# OSSIComms.net
KiCad netlist of a schematic drawn in EAGLE
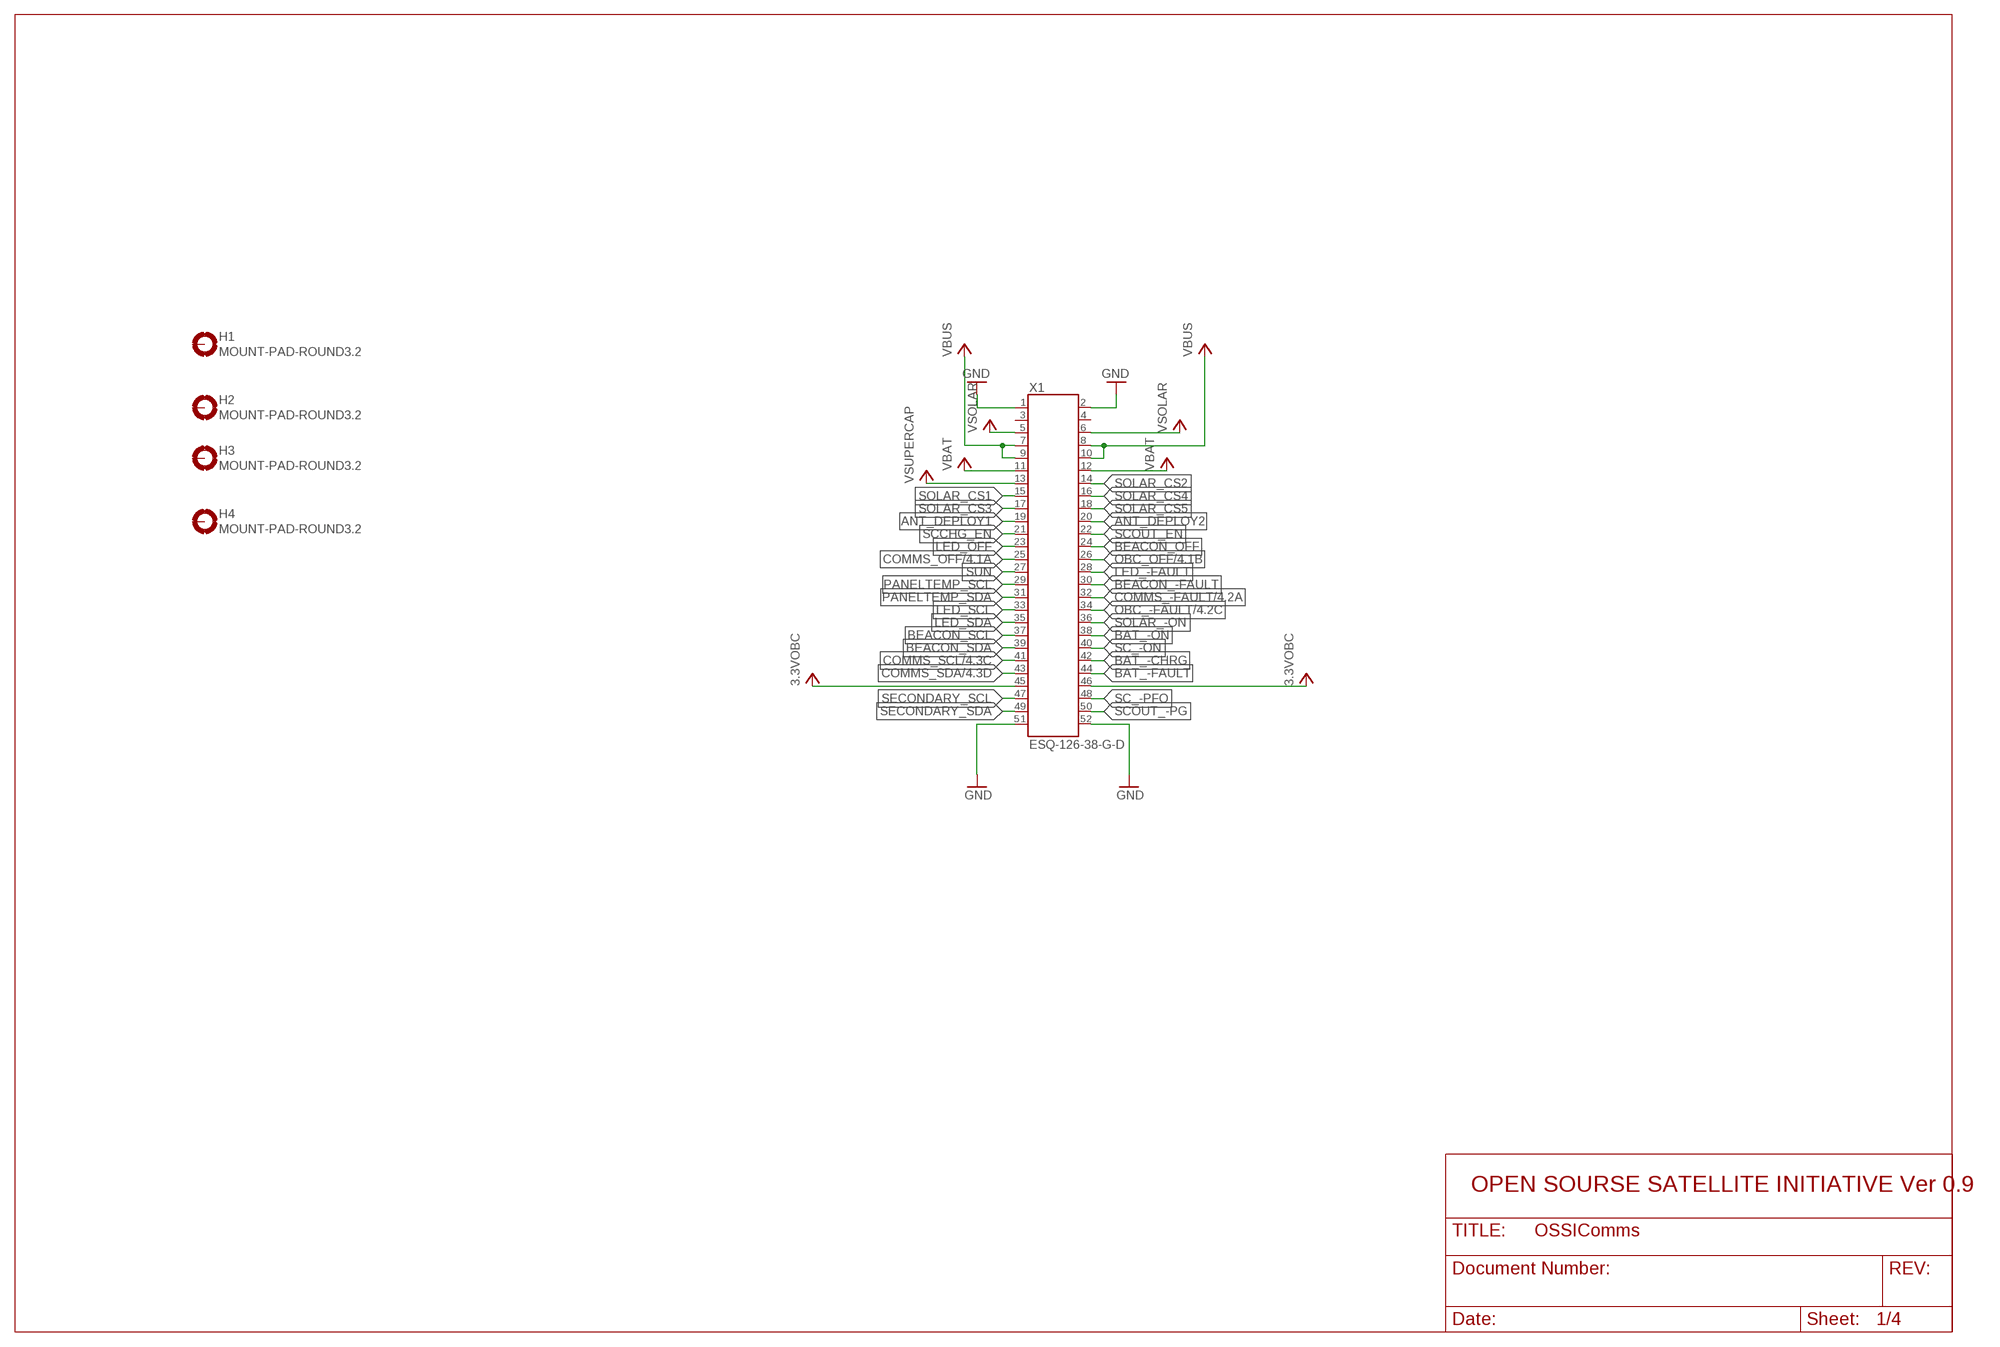
[diagram p0: schematic, sheet 1]
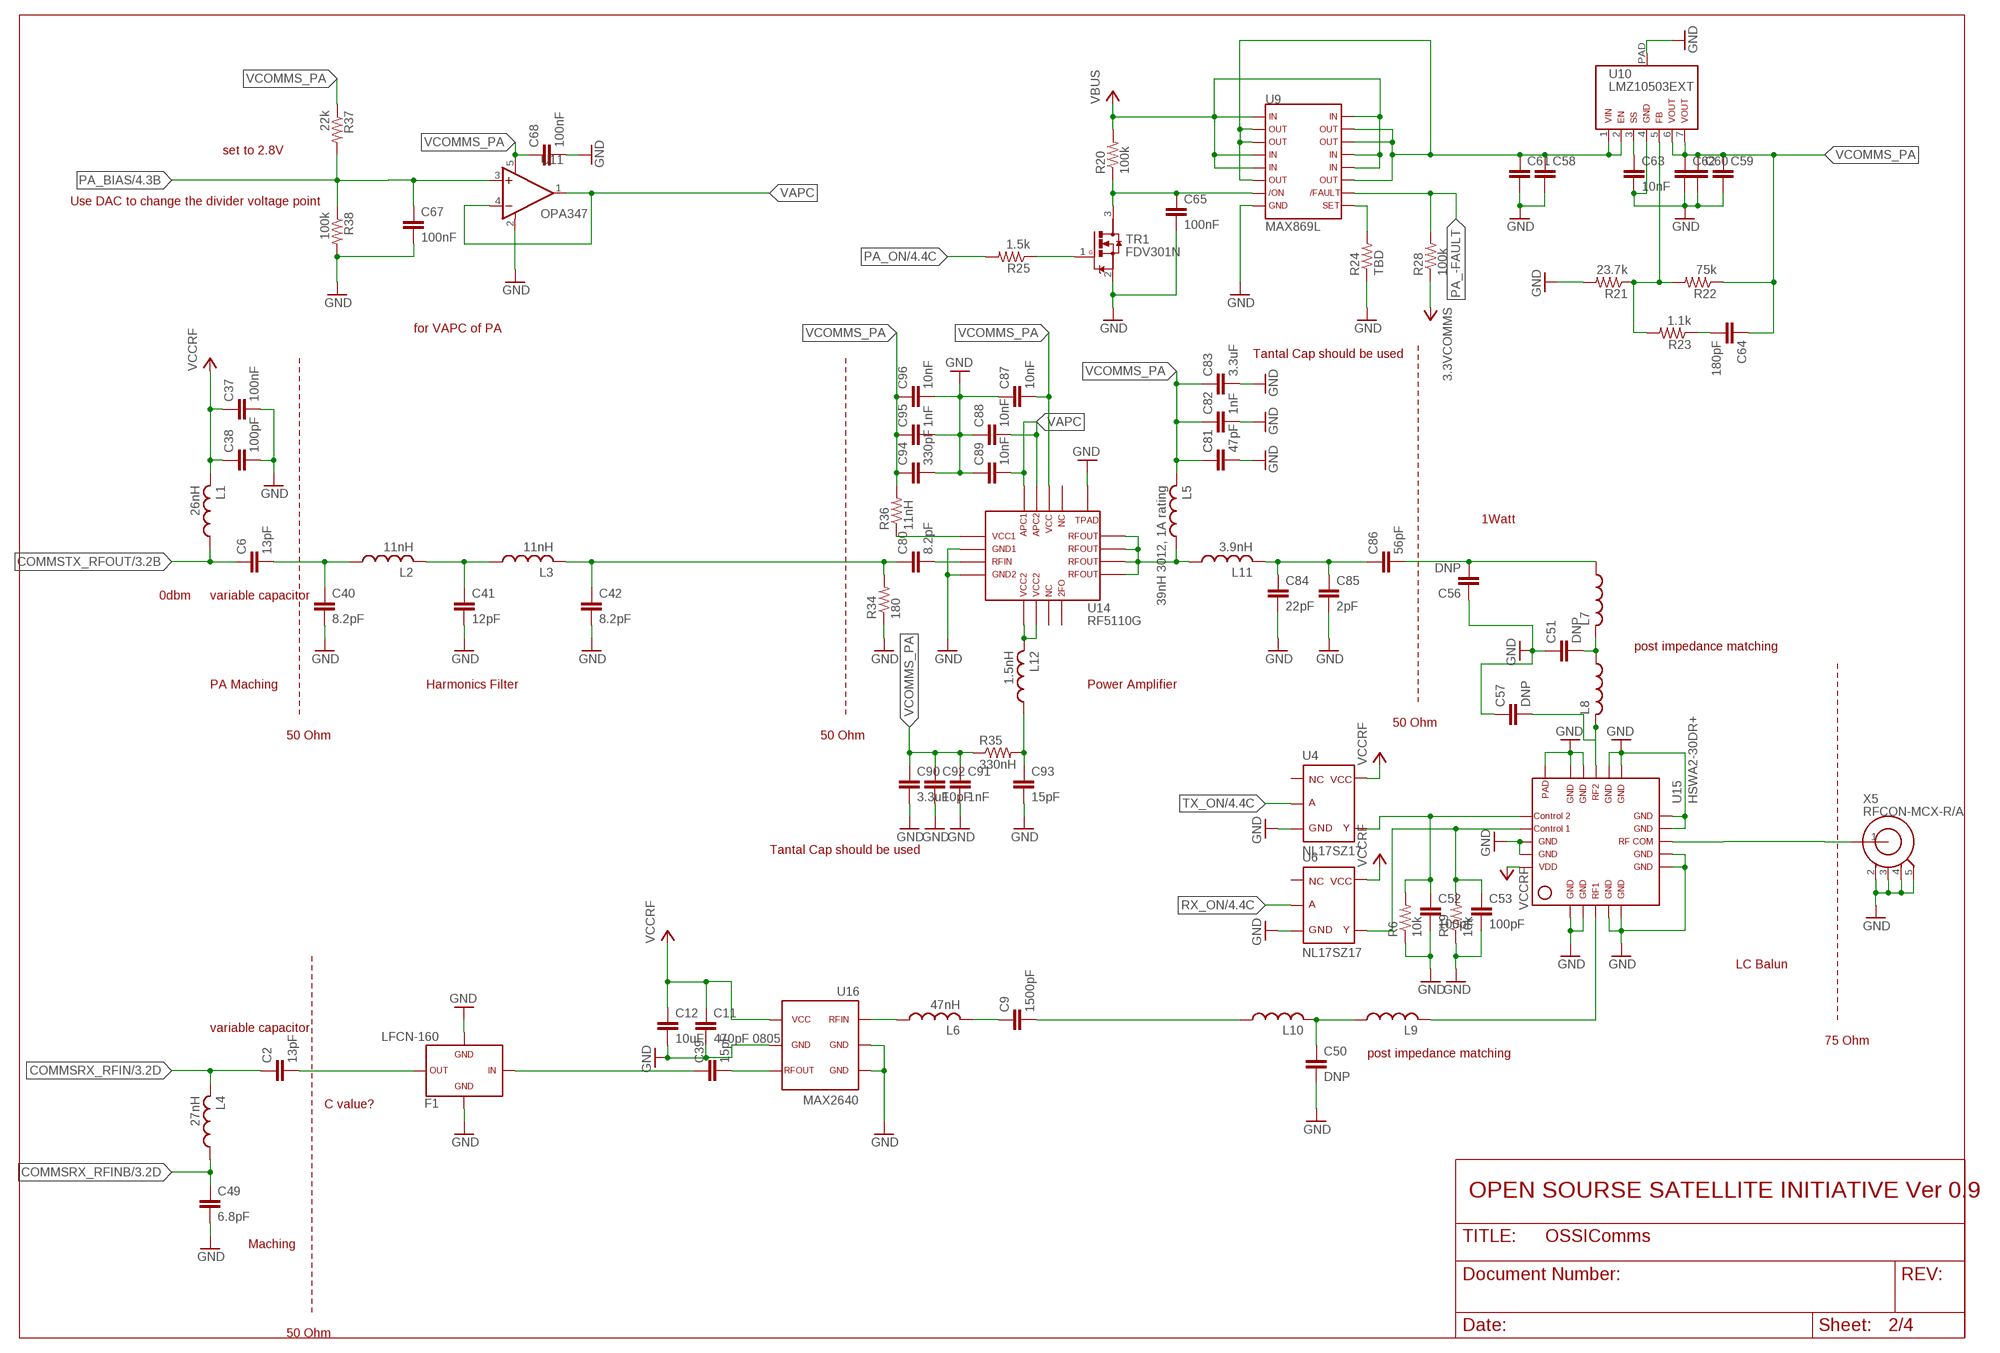
[diagram p1: schematic, sheet 2]
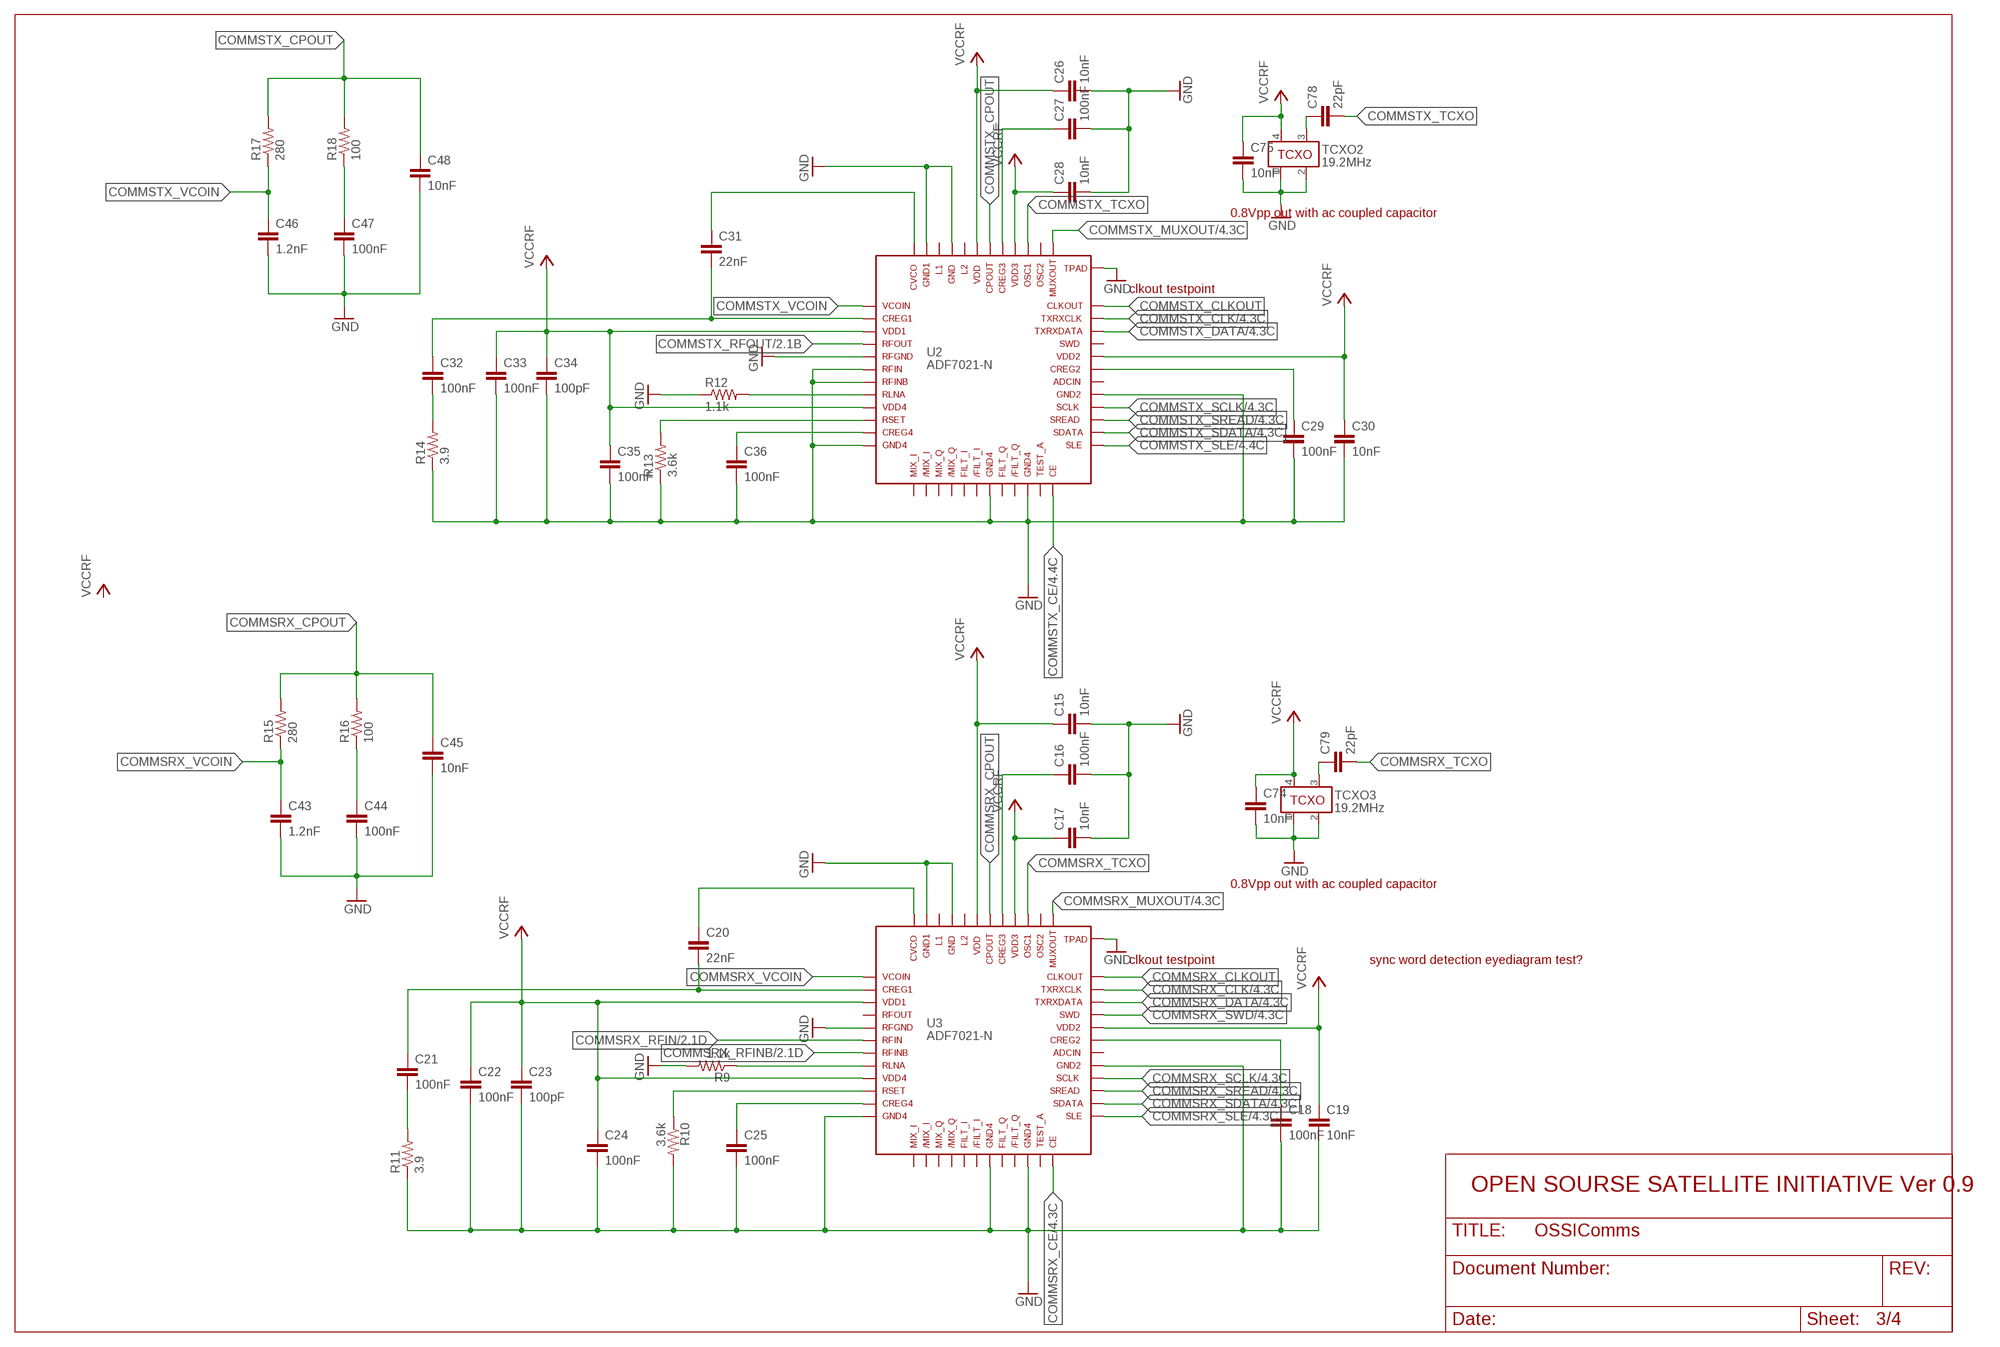
[diagram p2: schematic, sheet 3]
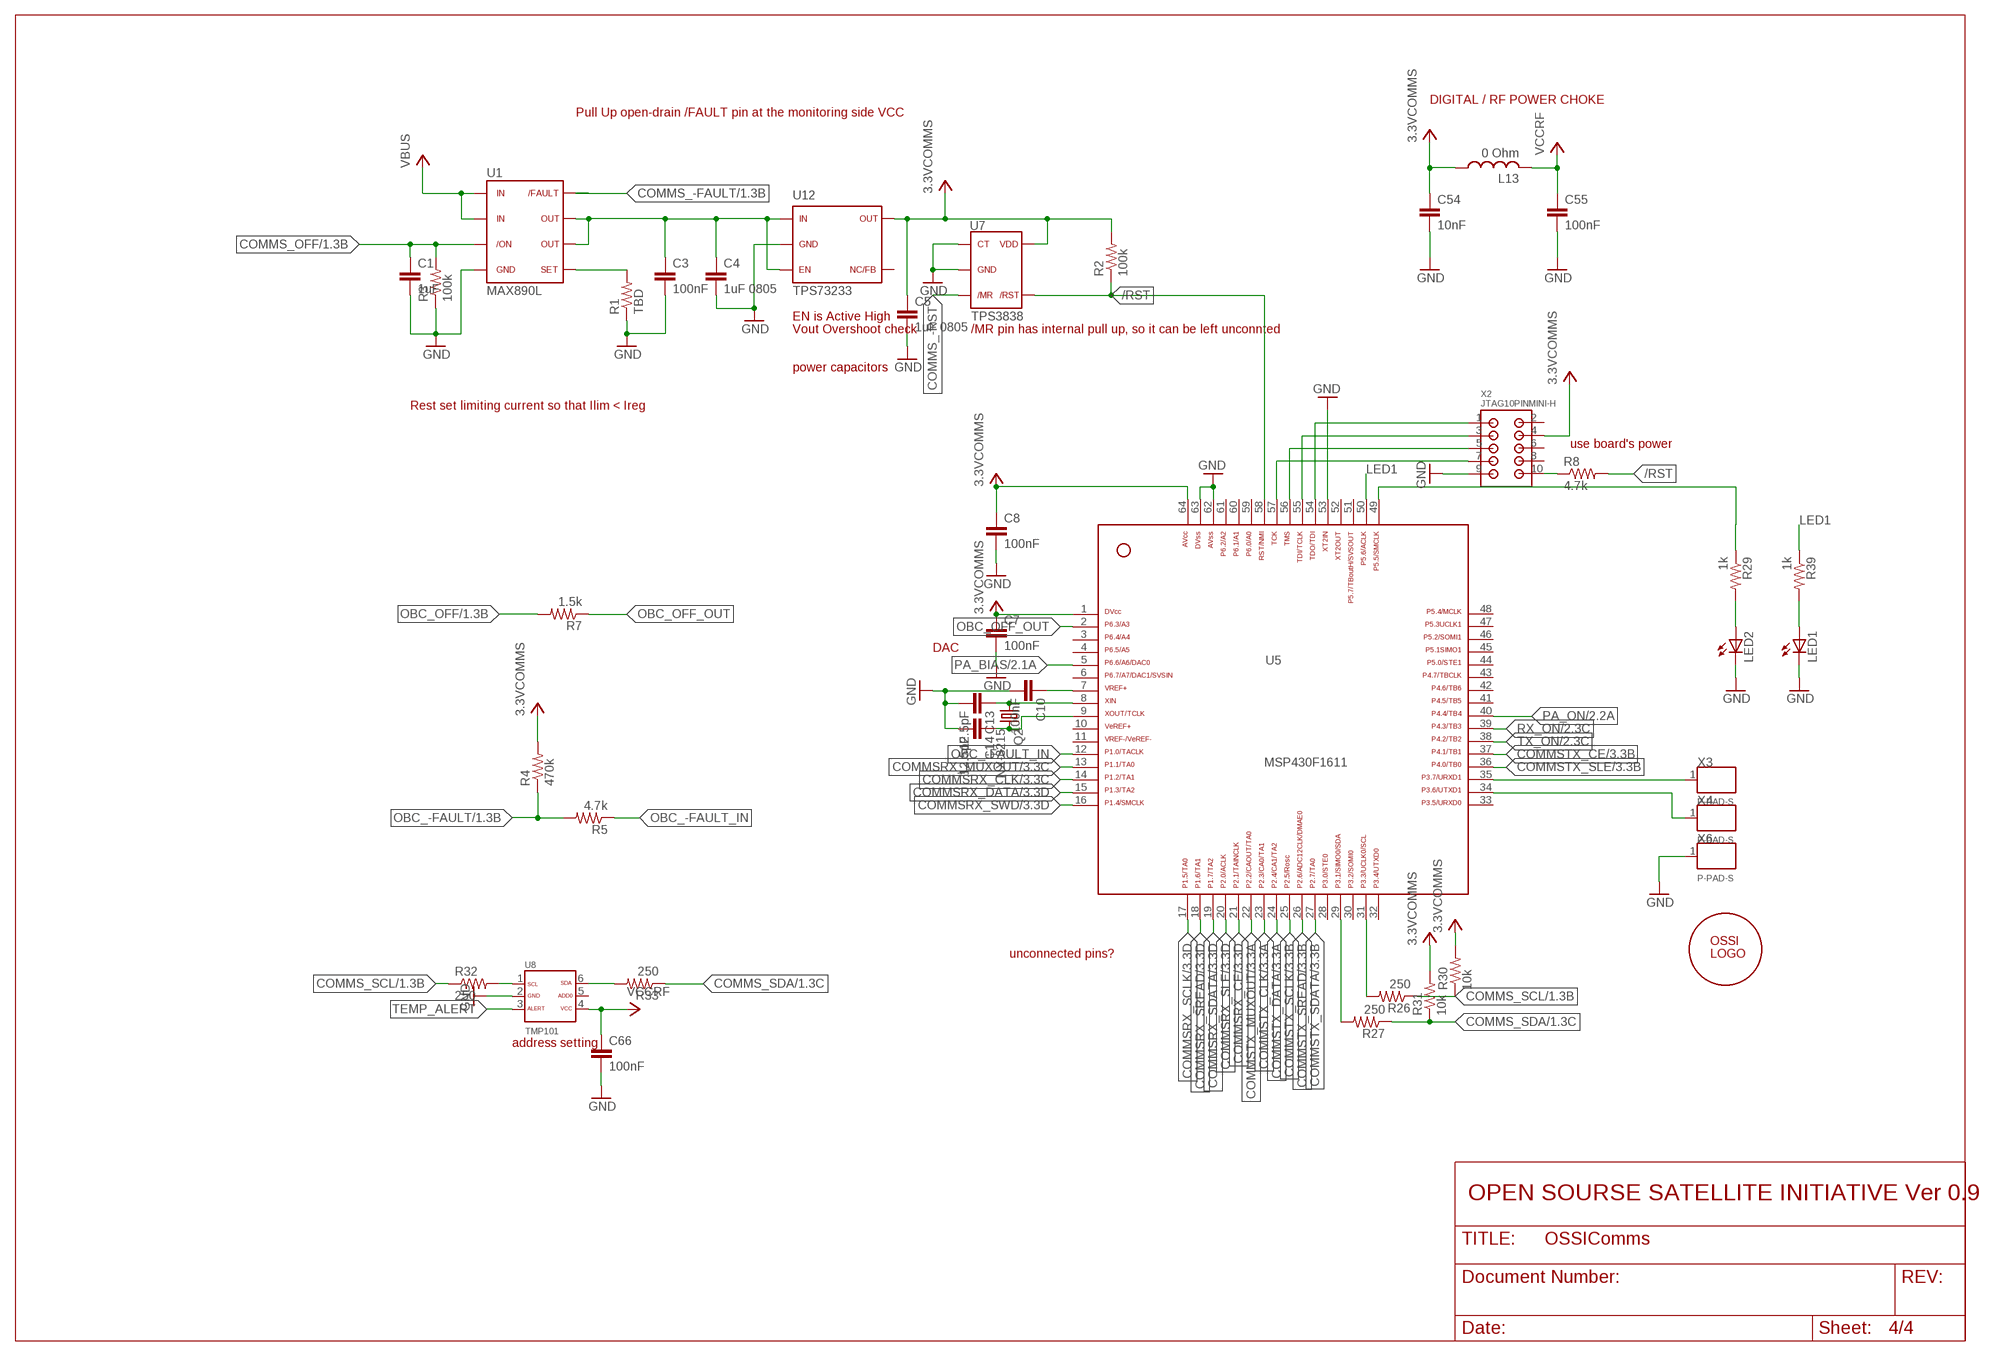
[diagram p3: schematic, sheet 4]

(export (version "E")
  (design (tool "Eeschema 10.0.6"))
  (components
    (comp (ref "C1")
      (value "1uF")
      (footprint "eagle-import:C0603(1608)")
      (libsource (lib "eagle-import") (part "C0603(1608)"))
    )
    (comp (ref "C3")
      (value "100nF")
      (footprint "eagle-import:C0603(1608)")
      (libsource (lib "eagle-import") (part "C0603(1608)"))
    )
    (comp (ref "C4")
      (value "1uF 0805")
      (footprint "eagle-import:C0805(2012)")
      (libsource (lib "eagle-import") (part "C0805(2012)"))
    )
    (comp (ref "C5")
      (value "1uF 0805")
      (footprint "eagle-import:C0805(2012)")
      (libsource (lib "eagle-import") (part "C0805(2012)"))
    )
    (comp (ref "C7")
      (value "100nF")
      (footprint "eagle-import:C0603(1608)")
      (libsource (lib "eagle-import") (part "C0603(1608)"))
    )
    (comp (ref "C8")
      (value "100nF")
      (footprint "eagle-import:C0603(1608)")
      (libsource (lib "eagle-import") (part "C0603(1608)"))
    )
    (comp (ref "C10")
      (value "100nF")
      (footprint "eagle-import:C0603(1608)")
      (libsource (lib "eagle-import") (part "C0603(1608)"))
    )
    (comp (ref "C13")
      (value "12.5pF")
      (footprint "eagle-import:C0603(1608)")
      (libsource (lib "eagle-import") (part "C0603(1608)"))
    )
    (comp (ref "C14")
      (value "12.5pF")
      (footprint "eagle-import:C0603(1608)")
      (libsource (lib "eagle-import") (part "C0603(1608)"))
    )
    (comp (ref "C54")
      (value "10nF")
      (footprint "eagle-import:C0603(1608)")
      (libsource (lib "eagle-import") (part "C0603(1608)"))
    )
    (comp (ref "C55")
      (value "100nF")
      (footprint "eagle-import:C0603(1608)")
      (libsource (lib "eagle-import") (part "C0603(1608)"))
    )
    (comp (ref "C66")
      (value "100nF")
      (footprint "eagle-import:C0603(1608)")
      (libsource (lib "eagle-import") (part "C0603(1608)"))
    )
    (comp (ref "L13")
      (value "0 Ohm")
      (footprint "eagle-import:L0805(2012)")
      (libsource (lib "eagle-import") (part "L0805(2012)"))
    )
    (comp (ref "LED1")
      (value "LEDCHIPLED_0603")
      (footprint "eagle-import:CHIPLED_0603")
      (libsource (lib "eagle-import") (part "LEDCHIPLED_0603"))
    )
    (comp (ref "LED2")
      (value "LEDCHIPLED_0603")
      (footprint "eagle-import:CHIPLED_0603")
      (libsource (lib "eagle-import") (part "LEDCHIPLED_0603"))
    )
    (comp (ref "Q2")
      (value "NX-3215")
      (footprint "eagle-import:NX-3215")
      (libsource (lib "eagle-import") (part "NX-3215"))
    )
    (comp (ref "R1")
      (value "TBD")
      (footprint "eagle-import:R0603(1608)")
      (libsource (lib "eagle-import") (part "R0603(1608)"))
    )
    (comp (ref "R2")
      (value "100k")
      (footprint "eagle-import:R0603(1608)")
      (libsource (lib "eagle-import") (part "R0603(1608)"))
    )
    (comp (ref "R3")
      (value "100k")
      (footprint "eagle-import:R0603(1608)")
      (libsource (lib "eagle-import") (part "R0603(1608)"))
    )
    (comp (ref "R4")
      (value "470k")
      (footprint "eagle-import:R0603(1608)")
      (libsource (lib "eagle-import") (part "R0603(1608)"))
    )
    (comp (ref "R5")
      (value "4.7k")
      (footprint "eagle-import:R0603(1608)")
      (libsource (lib "eagle-import") (part "R0603(1608)"))
    )
    (comp (ref "R7")
      (value "1.5k")
      (footprint "eagle-import:R0603(1608)")
      (libsource (lib "eagle-import") (part "R0603(1608)"))
    )
    (comp (ref "R8")
      (value "4.7k")
      (footprint "eagle-import:R0603(1608)")
      (libsource (lib "eagle-import") (part "R0603(1608)"))
    )
    (comp (ref "R26")
      (value "250")
      (footprint "eagle-import:R0603(1608)")
      (libsource (lib "eagle-import") (part "R0603(1608)"))
    )
    (comp (ref "R27")
      (value "250")
      (footprint "eagle-import:R0603(1608)")
      (libsource (lib "eagle-import") (part "R0603(1608)"))
    )
    (comp (ref "R29")
      (value "1k")
      (footprint "eagle-import:R0603(1608)")
      (libsource (lib "eagle-import") (part "R0603(1608)"))
    )
    (comp (ref "R30")
      (value "10k")
      (footprint "eagle-import:R0603(1608)")
      (libsource (lib "eagle-import") (part "R0603(1608)"))
    )
    (comp (ref "R31")
      (value "10k")
      (footprint "eagle-import:R0603(1608)")
      (libsource (lib "eagle-import") (part "R0603(1608)"))
    )
    (comp (ref "R32")
      (value "250")
      (footprint "eagle-import:R0603(1608)")
      (libsource (lib "eagle-import") (part "R0603(1608)"))
    )
    (comp (ref "R33")
      (value "250")
      (footprint "eagle-import:R0603(1608)")
      (libsource (lib "eagle-import") (part "R0603(1608)"))
    )
    (comp (ref "R39")
      (value "1k")
      (footprint "eagle-import:R0603(1608)")
      (libsource (lib "eagle-import") (part "R0603(1608)"))
    )
    (comp (ref "U$1")
      (value "OSSILOGORECT")
      (footprint "eagle-import:OSSILOGORECT1005")
      (libsource (lib "eagle-import") (part "OSSILOGORECT"))
    )
    (comp (ref "U1")
      (value "MAX890L")
      (footprint "eagle-import:SO8")
      (libsource (lib "eagle-import") (part "MAX890L"))
    )
    (comp (ref "U5")
      (value "MSP430F1611")
      (footprint "eagle-import:PM_PAG64")
      (libsource (lib "eagle-import") (part "MSP430F1611"))
    )
    (comp (ref "U7")
      (value "TPS3838")
      (footprint "eagle-import:SOT23-5DBV")
      (libsource (lib "eagle-import") (part "TPS3838"))
    )
    (comp (ref "U8")
      (value "TMP101")
      (footprint "eagle-import:SOT23-6DBV")
      (libsource (lib "eagle-import") (part "TMP101"))
    )
    (comp (ref "U12")
      (value "TPS73233")
      (footprint "eagle-import:SOT23-5DBV")
      (libsource (lib "eagle-import") (part "TPS73233"))
    )
    (comp (ref "X2")
      (value "JTAG10PINMINI-H")
      (footprint "eagle-import:M50-3200545")
      (libsource (lib "eagle-import") (part "JTAG10PINMINI-H"))
    )
    (comp (ref "X3")
      (value "P-PAD-S")
      (footprint "eagle-import:P-PAD-S")
      (libsource (lib "eagle-import") (part "P-PAD-S"))
    )
    (comp (ref "X4")
      (value "P-PAD-S")
      (footprint "eagle-import:P-PAD-S")
      (libsource (lib "eagle-import") (part "P-PAD-S"))
    )
    (comp (ref "X6")
      (value "P-PAD-S")
      (footprint "eagle-import:P-PAD-S")
      (libsource (lib "eagle-import") (part "P-PAD-S"))
    )
    (comp (ref "C2")
      (value "13pF")
      (footprint "eagle-import:C0603(1608)")
      (libsource (lib "eagle-import") (part "C0603(1608)"))
    )
    (comp (ref "C6")
      (value "13pF")
      (footprint "eagle-import:C0603(1608)")
      (libsource (lib "eagle-import") (part "C0603(1608)"))
    )
    (comp (ref "C9")
      (value "1500pF")
      (footprint "eagle-import:C0603(1608)")
      (libsource (lib "eagle-import") (part "C0603(1608)"))
    )
    (comp (ref "C11")
      (value "470pF 0805")
      (footprint "eagle-import:C0805(2012)")
      (libsource (lib "eagle-import") (part "C0805(2012)"))
    )
    (comp (ref "C12")
      (value "10uF")
      (footprint "eagle-import:C1206-GCM31")
      (libsource (lib "eagle-import") (part "C1206(3216)-GCM31"))
    )
    (comp (ref "C37")
      (value "100nF")
      (footprint "eagle-import:C0603(1608)")
      (libsource (lib "eagle-import") (part "C0603(1608)"))
    )
    (comp (ref "C38")
      (value "100pF")
      (footprint "eagle-import:C0603(1608)")
      (libsource (lib "eagle-import") (part "C0603(1608)"))
    )
    (comp (ref "C39")
      (value "15pF")
      (footprint "eagle-import:C0603(1608)")
      (libsource (lib "eagle-import") (part "C0603(1608)"))
    )
    (comp (ref "C40")
      (value "8.2pF")
      (footprint "eagle-import:C0603(1608)")
      (libsource (lib "eagle-import") (part "C0603(1608)"))
    )
    (comp (ref "C41")
      (value "12pF")
      (footprint "eagle-import:C0603(1608)")
      (libsource (lib "eagle-import") (part "C0603(1608)"))
    )
    (comp (ref "C42")
      (value "8.2pF")
      (footprint "eagle-import:C0603(1608)")
      (libsource (lib "eagle-import") (part "C0603(1608)"))
    )
    (comp (ref "C49")
      (value "6.8pF")
      (footprint "eagle-import:C0603(1608)")
      (libsource (lib "eagle-import") (part "C0603(1608)"))
    )
    (comp (ref "C50")
      (value "DNP")
      (footprint "eagle-import:C0603(1608)")
      (libsource (lib "eagle-import") (part "C0603(1608)"))
    )
    (comp (ref "C51")
      (value "DNP")
      (footprint "eagle-import:C0603(1608)")
      (libsource (lib "eagle-import") (part "C0603(1608)"))
    )
    (comp (ref "C52")
      (value "100pF")
      (footprint "eagle-import:C0603(1608)")
      (libsource (lib "eagle-import") (part "C0603(1608)"))
    )
    (comp (ref "C53")
      (value "100pF")
      (footprint "eagle-import:C0603(1608)")
      (libsource (lib "eagle-import") (part "C0603(1608)"))
    )
    (comp (ref "C56")
      (value "DNP")
      (footprint "eagle-import:C0603(1608)")
      (libsource (lib "eagle-import") (part "C0603(1608)"))
    )
    (comp (ref "C57")
      (value "DNP")
      (footprint "eagle-import:C0603(1608)")
      (libsource (lib "eagle-import") (part "C0603(1608)"))
    )
    (comp (ref "C58")
      (value "C1210(3225)-GCM32")
      (footprint "eagle-import:C1210-GCM32")
      (libsource (lib "eagle-import") (part "C1210(3225)-GCM32"))
    )
    (comp (ref "C59")
      (value "C1210(3225)-GCM32")
      (footprint "eagle-import:C1210-GCM32")
      (libsource (lib "eagle-import") (part "C1210(3225)-GCM32"))
    )
    (comp (ref "C60")
      (value "C1210(3225)-GCM32")
      (footprint "eagle-import:C1210-GCM32")
      (libsource (lib "eagle-import") (part "C1210(3225)-GCM32"))
    )
    (comp (ref "C61")
      (value "C1210(3225)-GCM32")
      (footprint "eagle-import:C1210-GCM32")
      (libsource (lib "eagle-import") (part "C1210(3225)-GCM32"))
    )
    (comp (ref "C62")
      (value "C0805(2012)")
      (footprint "eagle-import:C0805(2012)")
      (libsource (lib "eagle-import") (part "C0805(2012)"))
    )
    (comp (ref "C63")
      (value "10nF")
      (footprint "eagle-import:C0603(1608)")
      (libsource (lib "eagle-import") (part "C0603(1608)"))
    )
    (comp (ref "C64")
      (value "180pF")
      (footprint "eagle-import:C0603(1608)")
      (libsource (lib "eagle-import") (part "C0603(1608)"))
    )
    (comp (ref "C65")
      (value "100nF")
      (footprint "eagle-import:C0603(1608)")
      (libsource (lib "eagle-import") (part "C0603(1608)"))
    )
    (comp (ref "C67")
      (value "100nF")
      (footprint "eagle-import:C0603(1608)")
      (libsource (lib "eagle-import") (part "C0603(1608)"))
    )
    (comp (ref "C68")
      (value "100nF")
      (footprint "eagle-import:C0603(1608)")
      (libsource (lib "eagle-import") (part "C0603(1608)"))
    )
    (comp (ref "C80")
      (value "8.2pF")
      (footprint "eagle-import:C0603(1608)")
      (libsource (lib "eagle-import") (part "C0603(1608)"))
    )
    (comp (ref "C81")
      (value "47pF")
      (footprint "eagle-import:C0603(1608)")
      (libsource (lib "eagle-import") (part "C0603(1608)"))
    )
    (comp (ref "C82")
      (value "1nF")
      (footprint "eagle-import:C0603(1608)")
      (libsource (lib "eagle-import") (part "C0603(1608)"))
    )
    (comp (ref "C83")
      (value "3.3uF")
      (footprint "eagle-import:C1210-TMK325")
      (libsource (lib "eagle-import") (part "C1210(3225)-TMK325"))
    )
    (comp (ref "C84")
      (value "22pF")
      (footprint "eagle-import:C0603(1608)")
      (libsource (lib "eagle-import") (part "C0603(1608)"))
    )
    (comp (ref "C85")
      (value "2pF")
      (footprint "eagle-import:C0603(1608)")
      (libsource (lib "eagle-import") (part "C0603(1608)"))
    )
    (comp (ref "C86")
      (value "56pF")
      (footprint "eagle-import:C0603(1608)")
      (libsource (lib "eagle-import") (part "C0603(1608)"))
    )
    (comp (ref "C87")
      (value "10nF")
      (footprint "eagle-import:C0603(1608)")
      (libsource (lib "eagle-import") (part "C0603(1608)"))
    )
    (comp (ref "C88")
      (value "10nF")
      (footprint "eagle-import:C0603(1608)")
      (libsource (lib "eagle-import") (part "C0603(1608)"))
    )
    (comp (ref "C89")
      (value "10nF")
      (footprint "eagle-import:C0603(1608)")
      (libsource (lib "eagle-import") (part "C0603(1608)"))
    )
    (comp (ref "C90")
      (value "3.3uF")
      (footprint "eagle-import:C1210-TMK325")
      (libsource (lib "eagle-import") (part "C1210(3225)-TMK325"))
    )
    (comp (ref "C91")
      (value "1nF")
      (footprint "eagle-import:C0603(1608)")
      (libsource (lib "eagle-import") (part "C0603(1608)"))
    )
    (comp (ref "C92")
      (value "10pF")
      (footprint "eagle-import:C0603(1608)")
      (libsource (lib "eagle-import") (part "C0603(1608)"))
    )
    (comp (ref "C93")
      (value "15pF")
      (footprint "eagle-import:C0603(1608)")
      (libsource (lib "eagle-import") (part "C0603(1608)"))
    )
    (comp (ref "C94")
      (value "330pF")
      (footprint "eagle-import:C0603(1608)")
      (libsource (lib "eagle-import") (part "C0603(1608)"))
    )
    (comp (ref "C95")
      (value "1nF")
      (footprint "eagle-import:C0603(1608)")
      (libsource (lib "eagle-import") (part "C0603(1608)"))
    )
    (comp (ref "C96")
      (value "10nF")
      (footprint "eagle-import:C0603(1608)")
      (libsource (lib "eagle-import") (part "C0603(1608)"))
    )
    (comp (ref "F1")
      (value "LFCN-160")
      (footprint "eagle-import:LFCN")
      (libsource (lib "eagle-import") (part "LFCN-160"))
    )
    (comp (ref "L1")
      (value "26nH")
      (footprint "eagle-import:L0603(1608)")
      (libsource (lib "eagle-import") (part "L0603(1608)"))
    )
    (comp (ref "L2")
      (value "11nH")
      (footprint "eagle-import:L0603(1608)")
      (libsource (lib "eagle-import") (part "L0603(1608)"))
    )
    (comp (ref "L3")
      (value "11nH")
      (footprint "eagle-import:L0603(1608)")
      (libsource (lib "eagle-import") (part "L0603(1608)"))
    )
    (comp (ref "L4")
      (value "27nH")
      (footprint "eagle-import:L0603(1608)")
      (libsource (lib "eagle-import") (part "L0603(1608)"))
    )
    (comp (ref "L5")
      (value "39nH 3012, 1A rating")
      (footprint "eagle-import:NR3012")
      (libsource (lib "eagle-import") (part "LNR3012"))
    )
    (comp (ref "L6")
      (value "47nH")
      (footprint "eagle-import:L0603(1608)")
      (libsource (lib "eagle-import") (part "L0603(1608)"))
    )
    (comp (ref "L7")
      (value "L0603(1608)")
      (footprint "eagle-import:L0603(1608)")
      (libsource (lib "eagle-import") (part "L0603(1608)"))
    )
    (comp (ref "L8")
      (value "L0603(1608)")
      (footprint "eagle-import:L0603(1608)")
      (libsource (lib "eagle-import") (part "L0603(1608)"))
    )
    (comp (ref "L9")
      (value "L0603(1608)")
      (footprint "eagle-import:L0603(1608)")
      (libsource (lib "eagle-import") (part "L0603(1608)"))
    )
    (comp (ref "L10")
      (value "L0603(1608)")
      (footprint "eagle-import:L0603(1608)")
      (libsource (lib "eagle-import") (part "L0603(1608)"))
    )
    (comp (ref "L11")
      (value "3.9nH")
      (footprint "eagle-import:L0603(1608)")
      (libsource (lib "eagle-import") (part "L0603(1608)"))
    )
    (comp (ref "L12")
      (value "1.5nH")
      (footprint "eagle-import:L0603(1608)")
      (libsource (lib "eagle-import") (part "L0603(1608)"))
    )
    (comp (ref "R6")
      (value "10k")
      (footprint "eagle-import:R0603(1608)")
      (libsource (lib "eagle-import") (part "R0603(1608)"))
    )
    (comp (ref "R19")
      (value "10k")
      (footprint "eagle-import:R0603(1608)")
      (libsource (lib "eagle-import") (part "R0603(1608)"))
    )
    (comp (ref "R20")
      (value "100k")
      (footprint "eagle-import:R0603(1608)")
      (libsource (lib "eagle-import") (part "R0603(1608)"))
    )
    (comp (ref "R21")
      (value "23.7k")
      (footprint "eagle-import:R0603(1608)")
      (libsource (lib "eagle-import") (part "R0603(1608)"))
    )
    (comp (ref "R22")
      (value "75k")
      (footprint "eagle-import:R0603(1608)")
      (libsource (lib "eagle-import") (part "R0603(1608)"))
    )
    (comp (ref "R23")
      (value "1.1k")
      (footprint "eagle-import:R0603(1608)")
      (libsource (lib "eagle-import") (part "R0603(1608)"))
    )
    (comp (ref "R24")
      (value "TBD")
      (footprint "eagle-import:R0603(1608)")
      (libsource (lib "eagle-import") (part "R0603(1608)"))
    )
    (comp (ref "R25")
      (value "1.5k")
      (footprint "eagle-import:R0603(1608)")
      (libsource (lib "eagle-import") (part "R0603(1608)"))
    )
    (comp (ref "R28")
      (value "100k")
      (footprint "eagle-import:R0603(1608)")
      (libsource (lib "eagle-import") (part "R0603(1608)"))
    )
    (comp (ref "R34")
      (value "180")
      (footprint "eagle-import:R0603(1608)")
      (libsource (lib "eagle-import") (part "R0603(1608)"))
    )
    (comp (ref "R35")
      (value "330nH")
      (footprint "eagle-import:R0603(1608)")
      (libsource (lib "eagle-import") (part "R0603(1608)"))
    )
    (comp (ref "R36")
      (value "11nH")
      (footprint "eagle-import:R0603(1608)")
      (libsource (lib "eagle-import") (part "R0603(1608)"))
    )
    (comp (ref "R37")
      (value "22k")
      (footprint "eagle-import:R0603(1608)")
      (libsource (lib "eagle-import") (part "R0603(1608)"))
    )
    (comp (ref "R38")
      (value "100k")
      (footprint "eagle-import:R0603(1608)")
      (libsource (lib "eagle-import") (part "R0603(1608)"))
    )
    (comp (ref "TR1")
      (value "FDV301N")
      (footprint "eagle-import:SOT23")
      (libsource (lib "eagle-import") (part "FDV301N"))
    )
    (comp (ref "U4")
      (value "NL17SZ17")
      (footprint "eagle-import:SOT-553")
      (libsource (lib "eagle-import") (part "NL17SZ17"))
    )
    (comp (ref "U6")
      (value "NL17SZ17")
      (footprint "eagle-import:SOT-553")
      (libsource (lib "eagle-import") (part "NL17SZ17"))
    )
    (comp (ref "U9")
      (value "MAX869L")
      (footprint "eagle-import:16QSOP")
      (libsource (lib "eagle-import") (part "MAX869L"))
    )
    (comp (ref "U10")
      (value "LMZ10503EXT")
      (footprint "eagle-import:TO-PMOD-7")
      (libsource (lib "eagle-import") (part "LMZ10503EXT"))
    )
    (comp (ref "U11")
      (value "OPA347")
      (footprint "eagle-import:SOT23-5DBV")
      (libsource (lib "eagle-import") (part "OPA347"))
    )
    (comp (ref "U14")
      (value "RF5110G")
      (footprint "eagle-import:RF5110G")
      (libsource (lib "eagle-import") (part "RF5110G"))
    )
    (comp (ref "U15")
      (value "HSWA2-30DR+")
      (footprint "eagle-import:DG983-1")
      (libsource (lib "eagle-import") (part "HSWA2-30DR+"))
    )
    (comp (ref "U16")
      (value "MAX2640")
      (footprint "eagle-import:SOT23-6")
      (libsource (lib "eagle-import") (part "MAX2640"))
    )
    (comp (ref "X5")
      (value "RFCON-MCX-R/A")
      (footprint "eagle-import:MCX-R_A")
      (libsource (lib "eagle-import") (part "RFCON-MCX-R/A"))
    )
    (comp (ref "H1")
      (value "MOUNT-PAD-ROUND3.2")
      (footprint "eagle-import:3.2-PAD-ROUND")
      (libsource (lib "eagle-import") (part "MOUNT-PAD-ROUND3.2"))
    )
    (comp (ref "H2")
      (value "MOUNT-PAD-ROUND3.2")
      (footprint "eagle-import:3.2-PAD-ROUND")
      (libsource (lib "eagle-import") (part "MOUNT-PAD-ROUND3.2"))
    )
    (comp (ref "H3")
      (value "MOUNT-PAD-ROUND3.2")
      (footprint "eagle-import:3.2-PAD-ROUND")
      (libsource (lib "eagle-import") (part "MOUNT-PAD-ROUND3.2"))
    )
    (comp (ref "H4")
      (value "MOUNT-PAD-ROUND3.2")
      (footprint "eagle-import:3.2-PAD-ROUND")
      (libsource (lib "eagle-import") (part "MOUNT-PAD-ROUND3.2"))
    )
    (comp (ref "X1")
      (value "ESQ-126-38-G-D")
      (footprint "eagle-import:ESQ-126-XX-X-D")
      (libsource (lib "eagle-import") (part "ESQ-126-38-G-D"))
    )
    (comp (ref "C15")
      (value "10nF")
      (footprint "eagle-import:C0603(1608)")
      (libsource (lib "eagle-import") (part "C0603(1608)"))
    )
    (comp (ref "C16")
      (value "100nF")
      (footprint "eagle-import:C0603(1608)")
      (libsource (lib "eagle-import") (part "C0603(1608)"))
    )
    (comp (ref "C17")
      (value "10nF")
      (footprint "eagle-import:C0603(1608)")
      (libsource (lib "eagle-import") (part "C0603(1608)"))
    )
    (comp (ref "C18")
      (value "100nF")
      (footprint "eagle-import:C0603(1608)")
      (libsource (lib "eagle-import") (part "C0603(1608)"))
    )
    (comp (ref "C19")
      (value "10nF")
      (footprint "eagle-import:C0603(1608)")
      (libsource (lib "eagle-import") (part "C0603(1608)"))
    )
    (comp (ref "C20")
      (value "22nF")
      (footprint "eagle-import:C0603(1608)")
      (libsource (lib "eagle-import") (part "C0603(1608)"))
    )
    (comp (ref "C21")
      (value "100nF")
      (footprint "eagle-import:C0603(1608)")
      (libsource (lib "eagle-import") (part "C0603(1608)"))
    )
    (comp (ref "C22")
      (value "100nF")
      (footprint "eagle-import:C0603(1608)")
      (libsource (lib "eagle-import") (part "C0603(1608)"))
    )
    (comp (ref "C23")
      (value "100pF")
      (footprint "eagle-import:C0603(1608)")
      (libsource (lib "eagle-import") (part "C0603(1608)"))
    )
    (comp (ref "C24")
      (value "100nF")
      (footprint "eagle-import:C0603(1608)")
      (libsource (lib "eagle-import") (part "C0603(1608)"))
    )
    (comp (ref "C25")
      (value "100nF")
      (footprint "eagle-import:C0603(1608)")
      (libsource (lib "eagle-import") (part "C0603(1608)"))
    )
    (comp (ref "C26")
      (value "10nF")
      (footprint "eagle-import:C0603(1608)")
      (libsource (lib "eagle-import") (part "C0603(1608)"))
    )
    (comp (ref "C27")
      (value "100nF")
      (footprint "eagle-import:C0603(1608)")
      (libsource (lib "eagle-import") (part "C0603(1608)"))
    )
    (comp (ref "C28")
      (value "10nF")
      (footprint "eagle-import:C0603(1608)")
      (libsource (lib "eagle-import") (part "C0603(1608)"))
    )
    (comp (ref "C29")
      (value "100nF")
      (footprint "eagle-import:C0603(1608)")
      (libsource (lib "eagle-import") (part "C0603(1608)"))
    )
    (comp (ref "C30")
      (value "10nF")
      (footprint "eagle-import:C0603(1608)")
      (libsource (lib "eagle-import") (part "C0603(1608)"))
    )
    (comp (ref "C31")
      (value "22nF")
      (footprint "eagle-import:C0603(1608)")
      (libsource (lib "eagle-import") (part "C0603(1608)"))
    )
    (comp (ref "C32")
      (value "100nF")
      (footprint "eagle-import:C0603(1608)")
      (libsource (lib "eagle-import") (part "C0603(1608)"))
    )
    (comp (ref "C33")
      (value "100nF")
      (footprint "eagle-import:C0603(1608)")
      (libsource (lib "eagle-import") (part "C0603(1608)"))
    )
    (comp (ref "C34")
      (value "100pF")
      (footprint "eagle-import:C0603(1608)")
      (libsource (lib "eagle-import") (part "C0603(1608)"))
    )
    (comp (ref "C35")
      (value "100nF")
      (footprint "eagle-import:C0603(1608)")
      (libsource (lib "eagle-import") (part "C0603(1608)"))
    )
    (comp (ref "C36")
      (value "100nF")
      (footprint "eagle-import:C0603(1608)")
      (libsource (lib "eagle-import") (part "C0603(1608)"))
    )
    (comp (ref "C43")
      (value "1.2nF")
      (footprint "eagle-import:C0603(1608)")
      (libsource (lib "eagle-import") (part "C0603(1608)"))
    )
    (comp (ref "C44")
      (value "100nF")
      (footprint "eagle-import:C0603(1608)")
      (libsource (lib "eagle-import") (part "C0603(1608)"))
    )
    (comp (ref "C45")
      (value "10nF")
      (footprint "eagle-import:C0603(1608)")
      (libsource (lib "eagle-import") (part "C0603(1608)"))
    )
    (comp (ref "C46")
      (value "1.2nF")
      (footprint "eagle-import:C0603(1608)")
      (libsource (lib "eagle-import") (part "C0603(1608)"))
    )
    (comp (ref "C47")
      (value "100nF")
      (footprint "eagle-import:C0603(1608)")
      (libsource (lib "eagle-import") (part "C0603(1608)"))
    )
    (comp (ref "C48")
      (value "10nF")
      (footprint "eagle-import:C0603(1608)")
      (libsource (lib "eagle-import") (part "C0603(1608)"))
    )
    (comp (ref "C74")
      (value "10nF")
      (footprint "eagle-import:C0603(1608)")
      (libsource (lib "eagle-import") (part "C0603(1608)"))
    )
    (comp (ref "C75")
      (value "10nF")
      (footprint "eagle-import:C0603(1608)")
      (libsource (lib "eagle-import") (part "C0603(1608)"))
    )
    (comp (ref "C78")
      (value "22pF")
      (footprint "eagle-import:C0603(1608)")
      (libsource (lib "eagle-import") (part "C0603(1608)"))
    )
    (comp (ref "C79")
      (value "22pF")
      (footprint "eagle-import:C0603(1608)")
      (libsource (lib "eagle-import") (part "C0603(1608)"))
    )
    (comp (ref "R9")
      (value "1.1k")
      (footprint "eagle-import:R0603(1608)")
      (libsource (lib "eagle-import") (part "R0603(1608)"))
    )
    (comp (ref "R10")
      (value "3.6k")
      (footprint "eagle-import:R0603(1608)")
      (libsource (lib "eagle-import") (part "R0603(1608)"))
    )
    (comp (ref "R11")
      (value "3.9")
      (footprint "eagle-import:R0603(1608)")
      (libsource (lib "eagle-import") (part "R0603(1608)"))
    )
    (comp (ref "R12")
      (value "1.1k")
      (footprint "eagle-import:R0603(1608)")
      (libsource (lib "eagle-import") (part "R0603(1608)"))
    )
    (comp (ref "R13")
      (value "3.6k")
      (footprint "eagle-import:R0603(1608)")
      (libsource (lib "eagle-import") (part "R0603(1608)"))
    )
    (comp (ref "R14")
      (value "3.9")
      (footprint "eagle-import:R0603(1608)")
      (libsource (lib "eagle-import") (part "R0603(1608)"))
    )
    (comp (ref "R15")
      (value "280")
      (footprint "eagle-import:R0603(1608)")
      (libsource (lib "eagle-import") (part "R0603(1608)"))
    )
    (comp (ref "R16")
      (value "100")
      (footprint "eagle-import:R0603(1608)")
      (libsource (lib "eagle-import") (part "R0603(1608)"))
    )
    (comp (ref "R17")
      (value "280")
      (footprint "eagle-import:R0603(1608)")
      (libsource (lib "eagle-import") (part "R0603(1608)"))
    )
    (comp (ref "R18")
      (value "100")
      (footprint "eagle-import:R0603(1608)")
      (libsource (lib "eagle-import") (part "R0603(1608)"))
    )
    (comp (ref "TCXO2")
      (value "19.2MHz")
      (footprint "eagle-import:TCXO_M532")
      (libsource (lib "eagle-import") (part "TCXO-M532"))
    )
    (comp (ref "TCXO3")
      (value "19.2MHz")
      (footprint "eagle-import:TCXO_M532")
      (libsource (lib "eagle-import") (part "TCXO-M532"))
    )
    (comp (ref "U2")
      (value "ADF7021-N")
      (footprint "eagle-import:LFCSP48")
      (libsource (lib "eagle-import") (part "ADF7021-N"))
    )
    (comp (ref "U3")
      (value "ADF7021-N")
      (footprint "eagle-import:LFCSP48")
      (libsource (lib "eagle-import") (part "ADF7021-N"))
    )
  )
  (nets
    (net (code "1") (name "3.3VCOMMS") (class "Default")
      (node (ref "C5") (pin "1") (pinfunction "1_1") (pintype "passive"))
      (node (ref "C54") (pin "1") (pinfunction "1_1") (pintype "passive"))
      (node (ref "C7") (pin "1") (pinfunction "1_1") (pintype "passive"))
      (node (ref "C8") (pin "1") (pinfunction "1_1") (pintype "passive"))
      (node (ref "L13") (pin "1") (pinfunction "1_1") (pintype "passive"))
      (node (ref "R2") (pin "2") (pinfunction "2_2") (pintype "passive"))
      (node (ref "R28") (pin "1") (pinfunction "1_1") (pintype "passive"))
      (node (ref "R30") (pin "2") (pinfunction "2_2") (pintype "passive"))
      (node (ref "R31") (pin "2") (pinfunction "2_2") (pintype "passive"))
      (node (ref "R4") (pin "2") (pinfunction "2_2") (pintype "passive"))
      (node (ref "U12") (pin "5") (pinfunction "5_5") (pintype "power_in"))
      (node (ref "U5") (pin "1") (pinfunction "1_1") (pintype "power_in"))
      (node (ref "U5") (pin "64") (pinfunction "64_64") (pintype "power_in"))
      (node (ref "U7") (pin "5") (pinfunction "P$5_5") (pintype "power_in"))
      (node (ref "X2") (pin "4") (pinfunction "4_4") (pintype "bidirectional"))
    )
    (net (code "2") (name "3.3VOBC") (class "Default")
      (node (ref "X1") (pin "45") (pinfunction "45_45") (pintype "bidirectional"))
      (node (ref "X1") (pin "46") (pinfunction "46_46") (pintype "bidirectional"))
    )
    (net (code "3") (name "ANT_DEPLOY1") (class "Default")
      (node (ref "X1") (pin "19") (pinfunction "19_19") (pintype "bidirectional"))
    )
    (net (code "4") (name "ANT_DEPLOY2") (class "Default")
      (node (ref "X1") (pin "20") (pinfunction "20_20") (pintype "bidirectional"))
    )
    (net (code "5") (name "BAT_-CHRG") (class "Default")
      (node (ref "X1") (pin "42") (pinfunction "42_42") (pintype "bidirectional"))
    )
    (net (code "6") (name "BAT_-FAULT") (class "Default")
      (node (ref "X1") (pin "44") (pinfunction "44_44") (pintype "bidirectional"))
    )
    (net (code "7") (name "BAT_-ON") (class "Default")
      (node (ref "X1") (pin "38") (pinfunction "38_38") (pintype "bidirectional"))
    )
    (net (code "8") (name "BEACON_-FAULT") (class "Default")
      (node (ref "X1") (pin "30") (pinfunction "30_30") (pintype "bidirectional"))
    )
    (net (code "9") (name "BEACON_OFF") (class "Default")
      (node (ref "X1") (pin "24") (pinfunction "24_24") (pintype "bidirectional"))
    )
    (net (code "10") (name "BEACON_SCL") (class "Default")
      (node (ref "X1") (pin "37") (pinfunction "37_37") (pintype "bidirectional"))
    )
    (net (code "11") (name "BEACON_SDA") (class "Default")
      (node (ref "X1") (pin "39") (pinfunction "39_39") (pintype "bidirectional"))
    )
    (net (code "12") (name "COMMSRX_CE") (class "Default")
      (node (ref "U3") (pin "24") (pinfunction "P$24_24") (pintype "bidirectional"))
      (node (ref "U5") (pin "21") (pinfunction "21_21") (pintype "bidirectional"))
    )
    (net (code "13") (name "COMMSRX_CLK") (class "Default")
      (node (ref "U3") (pin "35") (pinfunction "P$35_35") (pintype "bidirectional"))
      (node (ref "U5") (pin "14") (pinfunction "14_14") (pintype "bidirectional"))
    )
    (net (code "14") (name "COMMSRX_CLKOUT") (class "Default")
      (node (ref "U3") (pin "36") (pinfunction "P$36_36") (pintype "bidirectional"))
    )
    (net (code "15") (name "COMMSRX_CPOUT") (class "Default")
      (node (ref "C45") (pin "1") (pinfunction "1_1") (pintype "passive"))
      (node (ref "R15") (pin "2") (pinfunction "2_2") (pintype "passive"))
      (node (ref "R16") (pin "2") (pinfunction "2_2") (pintype "passive"))
      (node (ref "U3") (pin "42") (pinfunction "P$42_42") (pintype "bidirectional"))
    )
    (net (code "16") (name "COMMSRX_DATA") (class "Default")
      (node (ref "U3") (pin "34") (pinfunction "P$34_34") (pintype "bidirectional"))
      (node (ref "U5") (pin "15") (pinfunction "15_15") (pintype "bidirectional"))
    )
    (net (code "17") (name "COMMSRX_MUXOUT") (class "Default")
      (node (ref "U3") (pin "37") (pinfunction "P$37_37") (pintype "bidirectional"))
      (node (ref "U5") (pin "13") (pinfunction "13_13") (pintype "bidirectional"))
    )
    (net (code "18") (name "COMMSRX_RFIN") (class "Default")
      (node (ref "C2") (pin "1") (pinfunction "1_1") (pintype "passive"))
      (node (ref "L4") (pin "2") (pinfunction "2_2") (pintype "passive"))
      (node (ref "U3") (pin "6") (pinfunction "P$6_6") (pintype "bidirectional"))
    )
    (net (code "19") (name "COMMSRX_RFINB") (class "Default")
      (node (ref "C49") (pin "1") (pinfunction "1_1") (pintype "passive"))
      (node (ref "L4") (pin "1") (pinfunction "1_1") (pintype "passive"))
      (node (ref "U3") (pin "7") (pinfunction "P$7_7") (pintype "bidirectional"))
    )
    (net (code "20") (name "COMMSRX_SCLK") (class "Default")
      (node (ref "U3") (pin "28") (pinfunction "P$28_28") (pintype "bidirectional"))
      (node (ref "U5") (pin "17") (pinfunction "17_17") (pintype "bidirectional"))
    )
    (net (code "21") (name "COMMSRX_SDATA") (class "Default")
      (node (ref "U3") (pin "26") (pinfunction "P$26_26") (pintype "bidirectional"))
      (node (ref "U5") (pin "19") (pinfunction "19_19") (pintype "bidirectional"))
    )
    (net (code "22") (name "COMMSRX_SLE") (class "Default")
      (node (ref "U3") (pin "25") (pinfunction "P$25_25") (pintype "bidirectional"))
      (node (ref "U5") (pin "20") (pinfunction "20_20") (pintype "bidirectional"))
    )
    (net (code "23") (name "COMMSRX_SREAD") (class "Default")
      (node (ref "U3") (pin "27") (pinfunction "P$27_27") (pintype "bidirectional"))
      (node (ref "U5") (pin "18") (pinfunction "18_18") (pintype "bidirectional"))
    )
    (net (code "24") (name "COMMSRX_SWD") (class "Default")
      (node (ref "U3") (pin "33") (pinfunction "P$33_33") (pintype "bidirectional"))
      (node (ref "U5") (pin "16") (pinfunction "16_16") (pintype "bidirectional"))
    )
    (net (code "25") (name "COMMSRX_TCXO") (class "Default")
      (node (ref "C79") (pin "2") (pinfunction "2_2") (pintype "passive"))
      (node (ref "U3") (pin "39") (pinfunction "P$39_39") (pintype "bidirectional"))
    )
    (net (code "26") (name "COMMSRX_VCOIN") (class "Default")
      (node (ref "C43") (pin "1") (pinfunction "1_1") (pintype "passive"))
      (node (ref "R15") (pin "1") (pinfunction "1_1") (pintype "passive"))
      (node (ref "U3") (pin "1") (pinfunction "P$1_1") (pintype "bidirectional"))
    )
    (net (code "27") (name "COMMSTX_CE") (class "Default")
      (node (ref "U2") (pin "24") (pinfunction "P$24_24") (pintype "bidirectional"))
      (node (ref "U5") (pin "37") (pinfunction "37_37") (pintype "bidirectional"))
    )
    (net (code "28") (name "COMMSTX_CLK") (class "Default")
      (node (ref "U2") (pin "35") (pinfunction "P$35_35") (pintype "bidirectional"))
      (node (ref "U5") (pin "23") (pinfunction "23_23") (pintype "bidirectional"))
    )
    (net (code "29") (name "COMMSTX_CLKOUT") (class "Default")
      (node (ref "U2") (pin "36") (pinfunction "P$36_36") (pintype "bidirectional"))
    )
    (net (code "30") (name "COMMSTX_CPOUT") (class "Default")
      (node (ref "C48") (pin "1") (pinfunction "1_1") (pintype "passive"))
      (node (ref "R17") (pin "2") (pinfunction "2_2") (pintype "passive"))
      (node (ref "R18") (pin "2") (pinfunction "2_2") (pintype "passive"))
      (node (ref "U2") (pin "42") (pinfunction "P$42_42") (pintype "bidirectional"))
    )
    (net (code "31") (name "COMMSTX_DATA") (class "Default")
      (node (ref "U2") (pin "34") (pinfunction "P$34_34") (pintype "bidirectional"))
      (node (ref "U5") (pin "24") (pinfunction "24_24") (pintype "bidirectional"))
    )
    (net (code "32") (name "COMMSTX_MUXOUT") (class "Default")
      (node (ref "U2") (pin "37") (pinfunction "P$37_37") (pintype "bidirectional"))
      (node (ref "U5") (pin "22") (pinfunction "22_22") (pintype "bidirectional"))
    )
    (net (code "33") (name "COMMSTX_RFOUT") (class "Default")
      (node (ref "C6") (pin "1") (pinfunction "1_1") (pintype "passive"))
      (node (ref "L1") (pin "1") (pinfunction "1_1") (pintype "passive"))
      (node (ref "U2") (pin "4") (pinfunction "P$4_4") (pintype "bidirectional"))
    )
    (net (code "34") (name "COMMSTX_SCLK") (class "Default")
      (node (ref "U2") (pin "28") (pinfunction "P$28_28") (pintype "bidirectional"))
      (node (ref "U5") (pin "25") (pinfunction "25_25") (pintype "bidirectional"))
    )
    (net (code "35") (name "COMMSTX_SDATA") (class "Default")
      (node (ref "U2") (pin "26") (pinfunction "P$26_26") (pintype "bidirectional"))
      (node (ref "U5") (pin "27") (pinfunction "27_27") (pintype "bidirectional"))
    )
    (net (code "36") (name "COMMSTX_SLE") (class "Default")
      (node (ref "U2") (pin "25") (pinfunction "P$25_25") (pintype "bidirectional"))
      (node (ref "U5") (pin "36") (pinfunction "36_36") (pintype "output"))
    )
    (net (code "37") (name "COMMSTX_SREAD") (class "Default")
      (node (ref "U2") (pin "27") (pinfunction "P$27_27") (pintype "bidirectional"))
      (node (ref "U5") (pin "26") (pinfunction "26_26") (pintype "bidirectional"))
    )
    (net (code "38") (name "COMMSTX_TCXO") (class "Default")
      (node (ref "C78") (pin "2") (pinfunction "2_2") (pintype "passive"))
      (node (ref "U2") (pin "39") (pinfunction "P$39_39") (pintype "bidirectional"))
    )
    (net (code "39") (name "COMMSTX_VCOIN") (class "Default")
      (node (ref "C46") (pin "1") (pinfunction "1_1") (pintype "passive"))
      (node (ref "R17") (pin "1") (pinfunction "1_1") (pintype "passive"))
      (node (ref "U2") (pin "1") (pinfunction "P$1_1") (pintype "bidirectional"))
    )
    (net (code "40") (name "COMMS_-FAULT") (class "Default")
      (node (ref "U1") (pin "8") (pinfunction "P$8_8") (pintype "output"))
      (node (ref "X1") (pin "32") (pinfunction "32_32") (pintype "bidirectional"))
    )
    (net (code "41") (name "COMMS_-RST") (class "Default")
      (node (ref "U7") (pin "3") (pinfunction "P$3_3") (pintype "input"))
    )
    (net (code "42") (name "COMMS_OFF") (class "Default")
      (node (ref "C1") (pin "1") (pinfunction "1_1") (pintype "passive"))
      (node (ref "R3") (pin "2") (pinfunction "2_2") (pintype "passive"))
      (node (ref "U1") (pin "3") (pinfunction "P$3_3") (pintype "input"))
      (node (ref "X1") (pin "25") (pinfunction "25_25") (pintype "bidirectional"))
    )
    (net (code "43") (name "COMMS_SCL") (class "Default")
      (node (ref "R26") (pin "1") (pinfunction "1_1") (pintype "passive"))
      (node (ref "R30") (pin "1") (pinfunction "1_1") (pintype "passive"))
      (node (ref "R32") (pin "1") (pinfunction "1_1") (pintype "passive"))
      (node (ref "X1") (pin "41") (pinfunction "41_41") (pintype "bidirectional"))
    )
    (net (code "44") (name "COMMS_SDA") (class "Default")
      (node (ref "R27") (pin "1") (pinfunction "1_1") (pintype "passive"))
      (node (ref "R31") (pin "1") (pinfunction "1_1") (pintype "passive"))
      (node (ref "R33") (pin "1") (pinfunction "1_1") (pintype "passive"))
      (node (ref "X1") (pin "43") (pinfunction "43_43") (pintype "bidirectional"))
    )
    (net (code "45") (name "GND") (class "Default")
      (node (ref "C1") (pin "2") (pinfunction "2_2") (pintype "passive"))
      (node (ref "C10") (pin "2") (pinfunction "2_2") (pintype "passive"))
      (node (ref "C11") (pin "2") (pinfunction "2_2") (pintype "passive"))
      (node (ref "C12") (pin "P$2") (pinfunction "2_P$2") (pintype "passive"))
      (node (ref "C13") (pin "2") (pinfunction "2_2") (pintype "passive"))
      (node (ref "C14") (pin "2") (pinfunction "2_2") (pintype "passive"))
      (node (ref "C15") (pin "2") (pinfunction "2_2") (pintype "passive"))
      (node (ref "C16") (pin "2") (pinfunction "2_2") (pintype "passive"))
      (node (ref "C17") (pin "2") (pinfunction "2_2") (pintype "passive"))
      (node (ref "C18") (pin "2") (pinfunction "2_2") (pintype "passive"))
      (node (ref "C19") (pin "2") (pinfunction "2_2") (pintype "passive"))
      (node (ref "C22") (pin "2") (pinfunction "2_2") (pintype "passive"))
      (node (ref "C23") (pin "2") (pinfunction "2_2") (pintype "passive"))
      (node (ref "C24") (pin "2") (pinfunction "2_2") (pintype "passive"))
      (node (ref "C25") (pin "2") (pinfunction "2_2") (pintype "passive"))
      (node (ref "C26") (pin "2") (pinfunction "2_2") (pintype "passive"))
      (node (ref "C27") (pin "2") (pinfunction "2_2") (pintype "passive"))
      (node (ref "C28") (pin "2") (pinfunction "2_2") (pintype "passive"))
      (node (ref "C29") (pin "2") (pinfunction "2_2") (pintype "passive"))
      (node (ref "C3") (pin "2") (pinfunction "2_2") (pintype "passive"))
      (node (ref "C30") (pin "2") (pinfunction "2_2") (pintype "passive"))
      (node (ref "C33") (pin "2") (pinfunction "2_2") (pintype "passive"))
      (node (ref "C34") (pin "2") (pinfunction "2_2") (pintype "passive"))
      (node (ref "C35") (pin "2") (pinfunction "2_2") (pintype "passive"))
      (node (ref "C36") (pin "2") (pinfunction "2_2") (pintype "passive"))
      (node (ref "C37") (pin "2") (pinfunction "2_2") (pintype "passive"))
      (node (ref "C38") (pin "2") (pinfunction "2_2") (pintype "passive"))
      (node (ref "C4") (pin "2") (pinfunction "2_2") (pintype "passive"))
      (node (ref "C40") (pin "2") (pinfunction "2_2") (pintype "passive"))
      (node (ref "C41") (pin "2") (pinfunction "2_2") (pintype "passive"))
      (node (ref "C42") (pin "2") (pinfunction "2_2") (pintype "passive"))
      (node (ref "C43") (pin "2") (pinfunction "2_2") (pintype "passive"))
      (node (ref "C44") (pin "2") (pinfunction "2_2") (pintype "passive"))
      (node (ref "C45") (pin "2") (pinfunction "2_2") (pintype "passive"))
      (node (ref "C46") (pin "2") (pinfunction "2_2") (pintype "passive"))
      (node (ref "C47") (pin "2") (pinfunction "2_2") (pintype "passive"))
      (node (ref "C48") (pin "2") (pinfunction "2_2") (pintype "passive"))
      (node (ref "C49") (pin "2") (pinfunction "2_2") (pintype "passive"))
      (node (ref "C5") (pin "2") (pinfunction "2_2") (pintype "passive"))
      (node (ref "C50") (pin "2") (pinfunction "2_2") (pintype "passive"))
      (node (ref "C51") (pin "1") (pinfunction "1_1") (pintype "passive"))
      (node (ref "C52") (pin "2") (pinfunction "2_2") (pintype "passive"))
      (node (ref "C53") (pin "2") (pinfunction "2_2") (pintype "passive"))
      (node (ref "C54") (pin "2") (pinfunction "2_2") (pintype "passive"))
      (node (ref "C55") (pin "2") (pinfunction "2_2") (pintype "passive"))
      (node (ref "C56") (pin "1") (pinfunction "1_1") (pintype "passive"))
      (node (ref "C57") (pin "1") (pinfunction "1_1") (pintype "passive"))
      (node (ref "C58") (pin "P$2") (pinfunction "2_P$2") (pintype "passive"))
      (node (ref "C59") (pin "P$2") (pinfunction "2_P$2") (pintype "passive"))
      (node (ref "C60") (pin "P$2") (pinfunction "2_P$2") (pintype "passive"))
      (node (ref "C61") (pin "P$2") (pinfunction "2_P$2") (pintype "passive"))
      (node (ref "C62") (pin "2") (pinfunction "2_2") (pintype "passive"))
      (node (ref "C63") (pin "2") (pinfunction "2_2") (pintype "passive"))
      (node (ref "C65") (pin "2") (pinfunction "2_2") (pintype "passive"))
      (node (ref "C66") (pin "2") (pinfunction "2_2") (pintype "passive"))
      (node (ref "C67") (pin "2") (pinfunction "2_2") (pintype "passive"))
      (node (ref "C68") (pin "2") (pinfunction "2_2") (pintype "passive"))
      (node (ref "C7") (pin "2") (pinfunction "2_2") (pintype "passive"))
      (node (ref "C74") (pin "2") (pinfunction "2_2") (pintype "passive"))
      (node (ref "C75") (pin "2") (pinfunction "2_2") (pintype "passive"))
      (node (ref "C8") (pin "2") (pinfunction "2_2") (pintype "passive"))
      (node (ref "C81") (pin "2") (pinfunction "2_2") (pintype "passive"))
      (node (ref "C82") (pin "2") (pinfunction "2_2") (pintype "passive"))
      (node (ref "C83") (pin "P$2") (pinfunction "2_P$2") (pintype "passive"))
      (node (ref "C84") (pin "2") (pinfunction "2_2") (pintype "passive"))
      (node (ref "C85") (pin "2") (pinfunction "2_2") (pintype "passive"))
      (node (ref "C87") (pin "1") (pinfunction "1_1") (pintype "passive"))
      (node (ref "C88") (pin "1") (pinfunction "1_1") (pintype "passive"))
      (node (ref "C89") (pin "1") (pinfunction "1_1") (pintype "passive"))
      (node (ref "C90") (pin "P$2") (pinfunction "2_P$2") (pintype "passive"))
      (node (ref "C91") (pin "2") (pinfunction "2_2") (pintype "passive"))
      (node (ref "C92") (pin "2") (pinfunction "2_2") (pintype "passive"))
      (node (ref "C93") (pin "2") (pinfunction "2_2") (pintype "passive"))
      (node (ref "C94") (pin "2") (pinfunction "2_2") (pintype "passive"))
      (node (ref "C95") (pin "2") (pinfunction "2_2") (pintype "passive"))
      (node (ref "C96") (pin "2") (pinfunction "2_2") (pintype "passive"))
      (node (ref "F1") (pin "2") (pinfunction "P$2_2") (pintype "power_in"))
      (node (ref "F1") (pin "4") (pinfunction "P$4_4") (pintype "power_in"))
      (node (ref "LED1") (pin "C") (pinfunction "C_C") (pintype "passive"))
      (node (ref "LED2") (pin "C") (pinfunction "C_C") (pintype "passive"))
      (node (ref "R1") (pin "1") (pinfunction "1_1") (pintype "passive"))
      (node (ref "R10") (pin "2") (pinfunction "2_2") (pintype "passive"))
      (node (ref "R11") (pin "1") (pinfunction "1_1") (pintype "passive"))
      (node (ref "R12") (pin "1") (pinfunction "1_1") (pintype "passive"))
      (node (ref "R13") (pin "1") (pinfunction "1_1") (pintype "passive"))
      (node (ref "R14") (pin "1") (pinfunction "1_1") (pintype "passive"))
      (node (ref "R19") (pin "1") (pinfunction "1_1") (pintype "passive"))
      (node (ref "R21") (pin "2") (pinfunction "2_2") (pintype "passive"))
      (node (ref "R24") (pin "1") (pinfunction "1_1") (pintype "passive"))
      (node (ref "R3") (pin "1") (pinfunction "1_1") (pintype "passive"))
      (node (ref "R34") (pin "1") (pinfunction "1_1") (pintype "passive"))
      (node (ref "R38") (pin "2") (pinfunction "2_2") (pintype "passive"))
      (node (ref "R6") (pin "1") (pinfunction "1_1") (pintype "passive"))
      (node (ref "R9") (pin "2") (pinfunction "2_2") (pintype "passive"))
      (node (ref "TCXO2") (pin "1") (pinfunction "P$1_1") (pintype "bidirectional"))
      (node (ref "TCXO2") (pin "2") (pinfunction "P$2_2") (pintype "bidirectional"))
      (node (ref "TCXO3") (pin "1") (pinfunction "P$1_1") (pintype "bidirectional"))
      (node (ref "TCXO3") (pin "2") (pinfunction "P$2_2") (pintype "bidirectional"))
      (node (ref "TR1") (pin "2") (pinfunction "S_2") (pintype "bidirectional"))
      (node (ref "U1") (pin "4") (pinfunction "P$4_4") (pintype "power_in"))
      (node (ref "U10") (pin "4") (pinfunction "P$4_4") (pintype "power_in"))
      (node (ref "U10") (pin "PAD") (pinfunction "P$8_PAD") (pintype "power_in"))
      (node (ref "U11") (pin "2") (pinfunction "V-_2") (pintype "power_in"))
      (node (ref "U12") (pin "2") (pinfunction "2_2") (pintype "power_in"))
      (node (ref "U14") (pin "2") (pinfunction "P$2_2") (pintype "bidirectional"))
      (node (ref "U14") (pin "4") (pinfunction "P$4_4") (pintype "bidirectional"))
      (node (ref "U14") (pin "TPAD") (pinfunction "P$17_TPAD") (pintype "bidirectional"))
      (node (ref "U15") (pin "1") (pinfunction "P$1_1") (pintype "power_in"))
      (node (ref "U15") (pin "10") (pinfunction "P$10_10") (pintype "power_in"))
      (node (ref "U15") (pin "11") (pinfunction "P$11_11") (pintype "power_in"))
      (node (ref "U15") (pin "12") (pinfunction "P$12_12") (pintype "power_in"))
      (node (ref "U15") (pin "14") (pinfunction "P$14_14") (pintype "power_in"))
      (node (ref "U15") (pin "15") (pinfunction "P$15_15") (pintype "power_in"))
      (node (ref "U15") (pin "18") (pinfunction "P$18_18") (pintype "power_in"))
      (node (ref "U15") (pin "19") (pinfunction "P$19_19") (pintype "power_in"))
      (node (ref "U15") (pin "2") (pinfunction "P$2_2") (pintype "power_in"))
      (node (ref "U15") (pin "4") (pinfunction "P$4_4") (pintype "power_in"))
      (node (ref "U15") (pin "5") (pinfunction "P$5_5") (pintype "power_in"))
      (node (ref "U15") (pin "6") (pinfunction "P$6_6") (pintype "power_in"))
      (node (ref "U15") (pin "7") (pinfunction "P$7_7") (pintype "power_in"))
      (node (ref "U15") (pin "9") (pinfunction "P$9_9") (pintype "power_in"))
      (node (ref "U15") (pin "PAD") (pinfunction "P$21_PAD") (pintype "input"))
      (node (ref "U16") (pin "2") (pinfunction "2_2") (pintype "power_in"))
      (node (ref "U16") (pin "3") (pinfunction "3_3") (pintype "power_in"))
      (node (ref "U16") (pin "5") (pinfunction "5_5") (pintype "power_in"))
      (node (ref "U2") (pin "12") (pinfunction "P$12_12") (pintype "bidirectional"))
      (node (ref "U2") (pin "19") (pinfunction "P$19_19") (pintype "bidirectional"))
      (node (ref "U2") (pin "22") (pinfunction "P$22_22") (pintype "bidirectional"))
      (node (ref "U2") (pin "29") (pinfunction "P$29_29") (pintype "bidirectional"))
      (node (ref "U2") (pin "45") (pinfunction "P$45_45") (pintype "bidirectional"))
      (node (ref "U2") (pin "47") (pinfunction "P$47_47") (pintype "bidirectional"))
      (node (ref "U2") (pin "5") (pinfunction "P$5_5") (pintype "bidirectional"))
      (node (ref "U2") (pin "6") (pinfunction "P$6_6") (pintype "bidirectional"))
      (node (ref "U2") (pin "7") (pinfunction "P$7_7") (pintype "bidirectional"))
      (node (ref "U2") (pin "EXP") (pinfunction "P$49_EXP") (pintype "bidirectional"))
      (node (ref "U3") (pin "12") (pinfunction "P$12_12") (pintype "bidirectional"))
      (node (ref "U3") (pin "19") (pinfunction "P$19_19") (pintype "bidirectional"))
      (node (ref "U3") (pin "22") (pinfunction "P$22_22") (pintype "bidirectional"))
      (node (ref "U3") (pin "29") (pinfunction "P$29_29") (pintype "bidirectional"))
      (node (ref "U3") (pin "45") (pinfunction "P$45_45") (pintype "bidirectional"))
      (node (ref "U3") (pin "47") (pinfunction "P$47_47") (pintype "bidirectional"))
      (node (ref "U3") (pin "5") (pinfunction "P$5_5") (pintype "bidirectional"))
      (node (ref "U3") (pin "EXP") (pinfunction "P$49_EXP") (pintype "bidirectional"))
      (node (ref "U4") (pin "3") (pinfunction "P$3_3") (pintype "power_in"))
      (node (ref "U5") (pin "53") (pinfunction "53_53") (pintype "input"))
      (node (ref "U5") (pin "62") (pinfunction "62_62") (pintype "power_in"))
      (node (ref "U5") (pin "63") (pinfunction "63_63") (pintype "power_in"))
      (node (ref "U6") (pin "3") (pinfunction "P$3_3") (pintype "power_in"))
      (node (ref "U7") (pin "1") (pinfunction "P$1_1") (pintype "bidirectional"))
      (node (ref "U7") (pin "2") (pinfunction "P$2_2") (pintype "power_in"))
      (node (ref "U8") (pin "2") (pinfunction "2_2") (pintype "bidirectional"))
      (node (ref "U9") (pin "8") (pinfunction "P$8_8") (pintype "power_in"))
      (node (ref "X1") (pin "1") (pinfunction "1_1") (pintype "bidirectional"))
      (node (ref "X1") (pin "2") (pinfunction "2_2") (pintype "bidirectional"))
      (node (ref "X1") (pin "51") (pinfunction "51_51") (pintype "bidirectional"))
      (node (ref "X1") (pin "52") (pinfunction "52_52") (pintype "bidirectional"))
      (node (ref "X2") (pin "9") (pinfunction "9_9") (pintype "bidirectional"))
      (node (ref "X5") (pin "2") (pinfunction "2_2") (pintype "power_in"))
      (node (ref "X5") (pin "3") (pinfunction "3_3") (pintype "power_in"))
      (node (ref "X5") (pin "4") (pinfunction "4_4") (pintype "power_in"))
      (node (ref "X5") (pin "5") (pinfunction "5_5") (pintype "power_in"))
      (node (ref "X6") (pin "1") (pinfunction "P$1_1") (pintype "bidirectional"))
    )
    (net (code "46") (name "LED1") (class "Default")
      (node (ref "R39") (pin "1") (pinfunction "1_1") (pintype "passive"))
      (node (ref "U5") (pin "50") (pinfunction "50_50") (pintype "bidirectional"))
    )
    (net (code "47") (name "LED_-FAULT") (class "Default")
      (node (ref "X1") (pin "28") (pinfunction "28_28") (pintype "bidirectional"))
    )
    (net (code "48") (name "LED_OFF") (class "Default")
      (node (ref "X1") (pin "23") (pinfunction "23_23") (pintype "bidirectional"))
    )
    (net (code "49") (name "LED_SCL") (class "Default")
      (node (ref "X1") (pin "33") (pinfunction "33_33") (pintype "bidirectional"))
    )
    (net (code "50") (name "LED_SDA") (class "Default")
      (node (ref "X1") (pin "35") (pinfunction "35_35") (pintype "bidirectional"))
    )
    (net (code "51") (name "Net-(C9-Pad1)") (class "Default")
      (node (ref "C9") (pin "1") (pinfunction "1_1") (pintype "passive"))
      (node (ref "L6") (pin "2") (pinfunction "2_2") (pintype "passive"))
    )
    (net (code "52") (name "Net-(C9-Pad2)") (class "Default")
      (node (ref "C9") (pin "2") (pinfunction "2_2") (pintype "passive"))
      (node (ref "L10") (pin "1") (pinfunction "1_1") (pintype "passive"))
    )
    (net (code "53") (name "Net-(C10-Pad1)") (class "Default")
      (node (ref "C10") (pin "1") (pinfunction "1_1") (pintype "passive"))
      (node (ref "U5") (pin "7") (pinfunction "7_7") (pintype "output"))
    )
    (net (code "54") (name "Net-(C13-Pad1)") (class "Default")
      (node (ref "C13") (pin "1") (pinfunction "1_1") (pintype "passive"))
      (node (ref "Q2") (pin "1") (pinfunction "1_1") (pintype "passive"))
      (node (ref "U5") (pin "8") (pinfunction "8_8") (pintype "input"))
    )
    (net (code "55") (name "Net-(C14-Pad1)") (class "Default")
      (node (ref "C14") (pin "1") (pinfunction "1_1") (pintype "passive"))
      (node (ref "Q2") (pin "2") (pinfunction "2_2") (pintype "passive"))
      (node (ref "U5") (pin "9") (pinfunction "9_9") (pintype "bidirectional"))
    )
    (net (code "56") (name "Net-(C21-Pad2)") (class "Default")
      (node (ref "C21") (pin "2") (pinfunction "2_2") (pintype "passive"))
      (node (ref "R11") (pin "2") (pinfunction "2_2") (pintype "passive"))
    )
    (net (code "57") (name "Net-(C32-Pad2)") (class "Default")
      (node (ref "C32") (pin "2") (pinfunction "2_2") (pintype "passive"))
      (node (ref "R14") (pin "2") (pinfunction "2_2") (pintype "passive"))
    )
    (net (code "58") (name "Net-(C39-Pad2)") (class "Default")
      (node (ref "C39") (pin "2") (pinfunction "2_2") (pintype "passive"))
      (node (ref "U16") (pin "4") (pinfunction "4_4") (pintype "output"))
    )
    (net (code "59") (name "Net-(C40-Pad1)") (class "Default")
      (node (ref "C40") (pin "1") (pinfunction "1_1") (pintype "passive"))
      (node (ref "C6") (pin "2") (pinfunction "2_2") (pintype "passive"))
      (node (ref "L2") (pin "1") (pinfunction "1_1") (pintype "passive"))
    )
    (net (code "60") (name "Net-(C41-Pad1)") (class "Default")
      (node (ref "C41") (pin "1") (pinfunction "1_1") (pintype "passive"))
      (node (ref "L2") (pin "2") (pinfunction "2_2") (pintype "passive"))
      (node (ref "L3") (pin "1") (pinfunction "1_1") (pintype "passive"))
    )
    (net (code "61") (name "Net-(C42-Pad1)") (class "Default")
      (node (ref "C42") (pin "1") (pinfunction "1_1") (pintype "passive"))
      (node (ref "C80") (pin "1") (pinfunction "1_1") (pintype "passive"))
      (node (ref "L3") (pin "2") (pinfunction "2_2") (pintype "passive"))
      (node (ref "R34") (pin "2") (pinfunction "2_2") (pintype "passive"))
    )
    (net (code "62") (name "Net-(C44-Pad1)") (class "Default")
      (node (ref "C44") (pin "1") (pinfunction "1_1") (pintype "passive"))
      (node (ref "R16") (pin "1") (pinfunction "1_1") (pintype "passive"))
    )
    (net (code "63") (name "Net-(C47-Pad1)") (class "Default")
      (node (ref "C47") (pin "1") (pinfunction "1_1") (pintype "passive"))
      (node (ref "R18") (pin "1") (pinfunction "1_1") (pintype "passive"))
    )
    (net (code "64") (name "Net-(C50-Pad1)") (class "Default")
      (node (ref "C50") (pin "1") (pinfunction "1_1") (pintype "passive"))
      (node (ref "L10") (pin "2") (pinfunction "2_2") (pintype "passive"))
      (node (ref "L9") (pin "1") (pinfunction "1_1") (pintype "passive"))
    )
    (net (code "65") (name "Net-(C51-Pad2)") (class "Default")
      (node (ref "C51") (pin "2") (pinfunction "2_2") (pintype "passive"))
      (node (ref "L7") (pin "2") (pinfunction "2_2") (pintype "passive"))
      (node (ref "L8") (pin "1") (pinfunction "1_1") (pintype "passive"))
    )
    (net (code "66") (name "Net-(C56-Pad2)") (class "Default")
      (node (ref "C56") (pin "2") (pinfunction "2_2") (pintype "passive"))
      (node (ref "C86") (pin "2") (pinfunction "2_2") (pintype "passive"))
      (node (ref "L7") (pin "1") (pinfunction "1_1") (pintype "passive"))
    )
    (net (code "67") (name "Net-(C58-1)") (class "Default")
      (node (ref "C58") (pin "P$1") (pinfunction "1_P$1") (pintype "passive"))
      (node (ref "C61") (pin "P$1") (pinfunction "1_P$1") (pintype "passive"))
      (node (ref "U10") (pin "1") (pinfunction "P$1_1") (pintype "power_in"))
      (node (ref "U10") (pin "2") (pinfunction "P$2_2") (pintype "input"))
      (node (ref "U9") (pin "11") (pinfunction "P$11_11") (pintype "power_in"))
      (node (ref "U9") (pin "14") (pinfunction "P$14_14") (pintype "power_in"))
      (node (ref "U9") (pin "15") (pinfunction "P$15_15") (pintype "power_in"))
      (node (ref "U9") (pin "2") (pinfunction "P$2_2") (pintype "power_in"))
      (node (ref "U9") (pin "3") (pinfunction "P$3_3") (pintype "power_in"))
      (node (ref "U9") (pin "6") (pinfunction "P$6_6") (pintype "power_in"))
    )
    (net (code "68") (name "Net-(C64-Pad2)") (class "Default")
      (node (ref "C64") (pin "2") (pinfunction "2_2") (pintype "passive"))
      (node (ref "R23") (pin "1") (pinfunction "1_1") (pintype "passive"))
    )
    (net (code "69") (name "Net-(C84-Pad1)") (class "Default")
      (node (ref "C84") (pin "1") (pinfunction "1_1") (pintype "passive"))
      (node (ref "C85") (pin "1") (pinfunction "1_1") (pintype "passive"))
      (node (ref "C86") (pin "1") (pinfunction "1_1") (pintype "passive"))
      (node (ref "L11") (pin "2") (pinfunction "2_2") (pintype "passive"))
    )
    (net (code "70") (name "Net-(C93-Pad1)") (class "Default")
      (node (ref "C93") (pin "1") (pinfunction "1_1") (pintype "passive"))
      (node (ref "L12") (pin "1") (pinfunction "1_1") (pintype "passive"))
      (node (ref "R35") (pin "2") (pinfunction "2_2") (pintype "passive"))
    )
    (net (code "71") (name "Net-(F1-P$1)") (class "Default")
      (node (ref "C39") (pin "1") (pinfunction "1_1") (pintype "passive"))
      (node (ref "F1") (pin "1") (pinfunction "P$1_1") (pintype "input"))
    )
    (net (code "72") (name "Net-(F1-P$3)") (class "Default")
      (node (ref "C2") (pin "2") (pinfunction "2_2") (pintype "passive"))
      (node (ref "F1") (pin "3") (pinfunction "P$3_3") (pintype "output"))
    )
    (net (code "73") (name "Net-(L5-1)") (class "Default")
      (node (ref "L11") (pin "1") (pinfunction "1_1") (pintype "passive"))
      (node (ref "L5") (pin "P$1") (pinfunction "1_P$1") (pintype "passive"))
      (node (ref "U14") (pin "10") (pinfunction "P$10_10") (pintype "bidirectional"))
      (node (ref "U14") (pin "11") (pinfunction "P$11_11") (pintype "bidirectional"))
      (node (ref "U14") (pin "12") (pinfunction "P$12_12") (pintype "bidirectional"))
      (node (ref "U14") (pin "9") (pinfunction "P$9_9") (pintype "bidirectional"))
    )
    (net (code "74") (name "Net-(L6-Pad1)") (class "Default")
      (node (ref "L6") (pin "1") (pinfunction "1_1") (pintype "passive"))
      (node (ref "U16") (pin "1") (pinfunction "1_1") (pintype "bidirectional"))
    )
    (net (code "75") (name "Net-(LED1-PadA)") (class "Default")
      (node (ref "LED1") (pin "A") (pinfunction "A_A") (pintype "passive"))
      (node (ref "R39") (pin "2") (pinfunction "2_2") (pintype "passive"))
    )
    (net (code "76") (name "Net-(LED2-PadA)") (class "Default")
      (node (ref "LED2") (pin "A") (pinfunction "A_A") (pintype "passive"))
      (node (ref "R29") (pin "2") (pinfunction "2_2") (pintype "passive"))
    )
    (net (code "77") (name "Net-(R8-Pad1)") (class "Default")
      (node (ref "R8") (pin "1") (pinfunction "1_1") (pintype "passive"))
      (node (ref "X2") (pin "10") (pinfunction "10_10") (pintype "bidirectional"))
    )
    (net (code "78") (name "Net-(R26-Pad2)") (class "Default")
      (node (ref "R26") (pin "2") (pinfunction "2_2") (pintype "passive"))
      (node (ref "U5") (pin "31") (pinfunction "31_31") (pintype "bidirectional"))
    )
    (net (code "79") (name "Net-(R27-Pad2)") (class "Default")
      (node (ref "R27") (pin "2") (pinfunction "2_2") (pintype "passive"))
      (node (ref "U5") (pin "29") (pinfunction "29_29") (pintype "bidirectional"))
    )
    (net (code "80") (name "Net-(R29-Pad1)") (class "Default")
      (node (ref "R29") (pin "1") (pinfunction "1_1") (pintype "passive"))
      (node (ref "U5") (pin "49") (pinfunction "49_49") (pintype "bidirectional"))
    )
    (net (code "81") (name "Net-(R32-Pad2)") (class "Default")
      (node (ref "R32") (pin "2") (pinfunction "2_2") (pintype "passive"))
      (node (ref "U8") (pin "1") (pinfunction "1_1") (pintype "bidirectional"))
    )
    (net (code "82") (name "Net-(R33-Pad2)") (class "Default")
      (node (ref "R33") (pin "2") (pinfunction "2_2") (pintype "passive"))
      (node (ref "U8") (pin "6") (pinfunction "6_6") (pintype "bidirectional"))
    )
    (net (code "83") (name "Net-(TCXO2-P$3)") (class "Default")
      (node (ref "C78") (pin "1") (pinfunction "1_1") (pintype "passive"))
      (node (ref "TCXO2") (pin "3") (pinfunction "P$3_3") (pintype "bidirectional"))
    )
    (net (code "84") (name "Net-(TCXO3-P$3)") (class "Default")
      (node (ref "C79") (pin "1") (pinfunction "1_1") (pintype "passive"))
      (node (ref "TCXO3") (pin "3") (pinfunction "P$3_3") (pintype "bidirectional"))
    )
    (net (code "85") (name "Net-(TR1-D)") (class "Default")
      (node (ref "C65") (pin "1") (pinfunction "1_1") (pintype "passive"))
      (node (ref "R20") (pin "1") (pinfunction "1_1") (pintype "passive"))
      (node (ref "TR1") (pin "3") (pinfunction "D_3") (pintype "bidirectional"))
      (node (ref "U9") (pin "7") (pinfunction "P$7_7") (pintype "input"))
    )
    (net (code "86") (name "Net-(TR1-G)") (class "Default")
      (node (ref "R25") (pin "1") (pinfunction "1_1") (pintype "passive"))
      (node (ref "TR1") (pin "1") (pinfunction "G_1") (pintype "bidirectional"))
    )
    (net (code "87") (name "Net-(U1-P$5)") (class "Default")
      (node (ref "R1") (pin "2") (pinfunction "2_2") (pintype "passive"))
      (node (ref "U1") (pin "5") (pinfunction "P$5_5") (pintype "passive"))
    )
    (net (code "88") (name "Net-(U1-P$6)") (class "Default")
      (node (ref "C3") (pin "1") (pinfunction "1_1") (pintype "passive"))
      (node (ref "C4") (pin "1") (pinfunction "1_1") (pintype "passive"))
      (node (ref "U1") (pin "6") (pinfunction "P$6_6") (pintype "output"))
      (node (ref "U1") (pin "7") (pinfunction "P$7_7") (pintype "output"))
      (node (ref "U12") (pin "1") (pinfunction "1_1") (pintype "power_in"))
      (node (ref "U12") (pin "3") (pinfunction "3_3") (pintype "input"))
    )
    (net (code "89") (name "Net-(U2-P$2)") (class "Default")
      (node (ref "C31") (pin "2") (pinfunction "2_2") (pintype "passive"))
      (node (ref "C32") (pin "1") (pinfunction "1_1") (pintype "passive"))
      (node (ref "U2") (pin "2") (pinfunction "P$2_2") (pintype "bidirectional"))
    )
    (net (code "90") (name "Net-(U2-P$8)") (class "Default")
      (node (ref "R12") (pin "2") (pinfunction "2_2") (pintype "passive"))
      (node (ref "U2") (pin "8") (pinfunction "P$8_8") (pintype "bidirectional"))
    )
    (net (code "91") (name "Net-(U2-P$10)") (class "Default")
      (node (ref "R13") (pin "2") (pinfunction "2_2") (pintype "passive"))
      (node (ref "U2") (pin "10") (pinfunction "P$10_10") (pintype "bidirectional"))
    )
    (net (code "92") (name "Net-(U2-P$11)") (class "Default")
      (node (ref "C36") (pin "1") (pinfunction "1_1") (pintype "passive"))
      (node (ref "U2") (pin "11") (pinfunction "P$11_11") (pintype "bidirectional"))
    )
    (net (code "93") (name "Net-(U2-P$31)") (class "Default")
      (node (ref "C29") (pin "1") (pinfunction "1_1") (pintype "passive"))
      (node (ref "U2") (pin "31") (pinfunction "P$31_31") (pintype "bidirectional"))
    )
    (net (code "94") (name "Net-(U2-P$41)") (class "Default")
      (node (ref "C27") (pin "1") (pinfunction "1_1") (pintype "passive"))
      (node (ref "U2") (pin "41") (pinfunction "P$41_41") (pintype "bidirectional"))
    )
    (net (code "95") (name "Net-(U2-P$48)") (class "Default")
      (node (ref "C31") (pin "1") (pinfunction "1_1") (pintype "passive"))
      (node (ref "U2") (pin "48") (pinfunction "P$48_48") (pintype "bidirectional"))
    )
    (net (code "96") (name "Net-(U3-P$2)") (class "Default")
      (node (ref "C20") (pin "2") (pinfunction "2_2") (pintype "passive"))
      (node (ref "C21") (pin "1") (pinfunction "1_1") (pintype "passive"))
      (node (ref "U3") (pin "2") (pinfunction "P$2_2") (pintype "bidirectional"))
    )
    (net (code "97") (name "Net-(U3-P$8)") (class "Default")
      (node (ref "R9") (pin "1") (pinfunction "1_1") (pintype "passive"))
      (node (ref "U3") (pin "8") (pinfunction "P$8_8") (pintype "bidirectional"))
    )
    (net (code "98") (name "Net-(U3-P$10)") (class "Default")
      (node (ref "R10") (pin "1") (pinfunction "1_1") (pintype "passive"))
      (node (ref "U3") (pin "10") (pinfunction "P$10_10") (pintype "bidirectional"))
    )
    (net (code "99") (name "Net-(U3-P$11)") (class "Default")
      (node (ref "C25") (pin "1") (pinfunction "1_1") (pintype "passive"))
      (node (ref "U3") (pin "11") (pinfunction "P$11_11") (pintype "bidirectional"))
    )
    (net (code "100") (name "Net-(U3-P$31)") (class "Default")
      (node (ref "C18") (pin "1") (pinfunction "1_1") (pintype "passive"))
      (node (ref "U3") (pin "31") (pinfunction "P$31_31") (pintype "bidirectional"))
    )
    (net (code "101") (name "Net-(U3-P$41)") (class "Default")
      (node (ref "C16") (pin "1") (pinfunction "1_1") (pintype "passive"))
      (node (ref "U3") (pin "41") (pinfunction "P$41_41") (pintype "bidirectional"))
    )
    (net (code "102") (name "Net-(U3-P$48)") (class "Default")
      (node (ref "C20") (pin "1") (pinfunction "1_1") (pintype "passive"))
      (node (ref "U3") (pin "48") (pinfunction "P$48_48") (pintype "bidirectional"))
    )
    (net (code "103") (name "Net-(U5-Pad54)") (class "Default")
      (node (ref "U5") (pin "54") (pinfunction "54_54") (pintype "bidirectional"))
      (node (ref "X2") (pin "1") (pinfunction "1_1") (pintype "bidirectional"))
    )
    (net (code "104") (name "Net-(U5-Pad55)") (class "Default")
      (node (ref "U5") (pin "55") (pinfunction "55_55") (pintype "input"))
      (node (ref "X2") (pin "3") (pinfunction "3_3") (pintype "bidirectional"))
    )
    (net (code "105") (name "Net-(U5-Pad56)") (class "Default")
      (node (ref "U5") (pin "56") (pinfunction "56_56") (pintype "input"))
      (node (ref "X2") (pin "5") (pinfunction "5_5") (pintype "bidirectional"))
    )
    (net (code "106") (name "Net-(U5-Pad57)") (class "Default")
      (node (ref "U5") (pin "57") (pinfunction "57_57") (pintype "input"))
      (node (ref "X2") (pin "7") (pinfunction "7_7") (pintype "bidirectional"))
    )
    (net (code "107") (name "Net-(U9-P$9)") (class "Default")
      (node (ref "R24") (pin "2") (pinfunction "2_2") (pintype "passive"))
      (node (ref "U9") (pin "9") (pinfunction "P$9_9") (pintype "passive"))
    )
    (net (code "108") (name "Net-(U10-P$3)") (class "Default")
      (node (ref "C63") (pin "1") (pinfunction "1_1") (pintype "passive"))
      (node (ref "U10") (pin "3") (pinfunction "P$3_3") (pintype "passive"))
    )
    (net (code "109") (name "Net-(U10-P$5)") (class "Default")
      (node (ref "R21") (pin "1") (pinfunction "1_1") (pintype "passive"))
      (node (ref "R22") (pin "2") (pinfunction "2_2") (pintype "passive"))
      (node (ref "R23") (pin "2") (pinfunction "2_2") (pintype "passive"))
      (node (ref "U10") (pin "5") (pinfunction "P$5_5") (pintype "input"))
    )
    (net (code "110") (name "Net-(U14-P$1)") (class "Default")
      (node (ref "R36") (pin "1") (pinfunction "1_1") (pintype "passive"))
      (node (ref "U14") (pin "1") (pinfunction "P$1_1") (pintype "bidirectional"))
    )
    (net (code "111") (name "Net-(U14-P$3)") (class "Default")
      (node (ref "C80") (pin "2") (pinfunction "2_2") (pintype "passive"))
      (node (ref "U14") (pin "3") (pinfunction "P$3_3") (pintype "bidirectional"))
    )
    (net (code "112") (name "Net-(U14-P$5)") (class "Default")
      (node (ref "L12") (pin "2") (pinfunction "2_2") (pintype "passive"))
      (node (ref "U14") (pin "5") (pinfunction "P$5_5") (pintype "bidirectional"))
      (node (ref "U14") (pin "6") (pinfunction "P$6_6") (pintype "bidirectional"))
    )
    (net (code "113") (name "Net-(U15-P$3)") (class "Default")
      (node (ref "L9") (pin "2") (pinfunction "2_2") (pintype "passive"))
      (node (ref "U15") (pin "3") (pinfunction "P$3_3") (pintype "bidirectional"))
    )
    (net (code "114") (name "Net-(U15-P$8)") (class "Default")
      (node (ref "U15") (pin "8") (pinfunction "P$8_8") (pintype "bidirectional"))
      (node (ref "X5") (pin "1") (pinfunction "1_1") (pintype "bidirectional"))
    )
    (net (code "115") (name "Net-(U15-P$13)") (class "Default")
      (node (ref "C57") (pin "2") (pinfunction "2_2") (pintype "passive"))
      (node (ref "L8") (pin "2") (pinfunction "2_2") (pintype "passive"))
      (node (ref "U15") (pin "13") (pinfunction "P$13_13") (pintype "bidirectional"))
    )
    (net (code "116") (name "Net-(U15-P$16)") (class "Default")
      (node (ref "C52") (pin "1") (pinfunction "1_1") (pintype "passive"))
      (node (ref "R6") (pin "2") (pinfunction "2_2") (pintype "passive"))
      (node (ref "U15") (pin "16") (pinfunction "P$16_16") (pintype "input"))
      (node (ref "U4") (pin "4") (pinfunction "P$4_4") (pintype "output"))
    )
    (net (code "117") (name "Net-(U15-P$17)") (class "Default")
      (node (ref "C53") (pin "1") (pinfunction "1_1") (pintype "passive"))
      (node (ref "R19") (pin "2") (pinfunction "2_2") (pintype "passive"))
      (node (ref "U15") (pin "17") (pinfunction "P$17_17") (pintype "input"))
      (node (ref "U6") (pin "4") (pinfunction "P$4_4") (pintype "output"))
    )
    (net (code "118") (name "Net-(X3-P$1)") (class "Default")
      (node (ref "U5") (pin "35") (pinfunction "35_35") (pintype "bidirectional"))
      (node (ref "X3") (pin "1") (pinfunction "P$1_1") (pintype "bidirectional"))
    )
    (net (code "119") (name "Net-(X4-P$1)") (class "Default")
      (node (ref "U5") (pin "34") (pinfunction "34_34") (pintype "bidirectional"))
      (node (ref "X4") (pin "1") (pinfunction "P$1_1") (pintype "bidirectional"))
    )
    (net (code "120") (name "OBC_-FAULT") (class "Default")
      (node (ref "R4") (pin "1") (pinfunction "1_1") (pintype "passive"))
      (node (ref "R5") (pin "2") (pinfunction "2_2") (pintype "passive"))
      (node (ref "X1") (pin "34") (pinfunction "34_34") (pintype "bidirectional"))
    )
    (net (code "121") (name "OBC_-FAULT_IN") (class "Default")
      (node (ref "R5") (pin "1") (pinfunction "1_1") (pintype "passive"))
      (node (ref "U5") (pin "12") (pinfunction "12_12") (pintype "bidirectional"))
    )
    (net (code "122") (name "OBC_OFF") (class "Default")
      (node (ref "R7") (pin "2") (pinfunction "2_2") (pintype "passive"))
      (node (ref "X1") (pin "26") (pinfunction "26_26") (pintype "bidirectional"))
    )
    (net (code "123") (name "OBC_OFF_OUT") (class "Default")
      (node (ref "R7") (pin "1") (pinfunction "1_1") (pintype "passive"))
      (node (ref "U5") (pin "2") (pinfunction "2_2") (pintype "bidirectional"))
    )
    (net (code "124") (name "PANELTEMP_SCL") (class "Default")
      (node (ref "X1") (pin "29") (pinfunction "29_29") (pintype "bidirectional"))
    )
    (net (code "125") (name "PANELTEMP_SDA") (class "Default")
      (node (ref "X1") (pin "31") (pinfunction "31_31") (pintype "bidirectional"))
    )
    (net (code "126") (name "PA_-FAULT") (class "Default")
      (node (ref "R28") (pin "2") (pinfunction "2_2") (pintype "passive"))
      (node (ref "U9") (pin "10") (pinfunction "P$10_10") (pintype "output"))
    )
    (net (code "127") (name "PA_BIAS") (class "Default")
      (node (ref "C67") (pin "1") (pinfunction "1_1") (pintype "passive"))
      (node (ref "R37") (pin "2") (pinfunction "2_2") (pintype "passive"))
      (node (ref "R38") (pin "1") (pinfunction "1_1") (pintype "passive"))
      (node (ref "U11") (pin "3") (pinfunction "+IN_3") (pintype "input"))
      (node (ref "U5") (pin "5") (pinfunction "5_5") (pintype "bidirectional"))
    )
    (net (code "128") (name "PA_ON") (class "Default")
      (node (ref "R25") (pin "2") (pinfunction "2_2") (pintype "passive"))
      (node (ref "U5") (pin "40") (pinfunction "40_40") (pintype "input"))
    )
    (net (code "129") (name "RX_ON") (class "Default")
      (node (ref "U5") (pin "39") (pinfunction "39_39") (pintype "bidirectional"))
      (node (ref "U6") (pin "2") (pinfunction "P$2_2") (pintype "input"))
    )
    (net (code "130") (name "SCCHG_EN") (class "Default")
      (node (ref "X1") (pin "21") (pinfunction "21_21") (pintype "bidirectional"))
    )
    (net (code "131") (name "SCOUT_-PG") (class "Default")
      (node (ref "X1") (pin "50") (pinfunction "50_50") (pintype "bidirectional"))
    )
    (net (code "132") (name "SCOUT_EN") (class "Default")
      (node (ref "X1") (pin "22") (pinfunction "22_22") (pintype "bidirectional"))
    )
    (net (code "133") (name "SC_-ON") (class "Default")
      (node (ref "X1") (pin "40") (pinfunction "40_40") (pintype "bidirectional"))
    )
    (net (code "134") (name "SC_-PFO") (class "Default")
      (node (ref "X1") (pin "48") (pinfunction "48_48") (pintype "bidirectional"))
    )
    (net (code "135") (name "SECONDARY_SCL") (class "Default")
      (node (ref "X1") (pin "47") (pinfunction "47_47") (pintype "bidirectional"))
    )
    (net (code "136") (name "SECONDARY_SDA") (class "Default")
      (node (ref "X1") (pin "49") (pinfunction "49_49") (pintype "bidirectional"))
    )
    (net (code "137") (name "SOLAR_-ON") (class "Default")
      (node (ref "X1") (pin "36") (pinfunction "36_36") (pintype "bidirectional"))
    )
    (net (code "138") (name "SOLAR_CS1") (class "Default")
      (node (ref "X1") (pin "15") (pinfunction "15_15") (pintype "bidirectional"))
    )
    (net (code "139") (name "SOLAR_CS2") (class "Default")
      (node (ref "X1") (pin "14") (pinfunction "14_14") (pintype "bidirectional"))
    )
    (net (code "140") (name "SOLAR_CS3") (class "Default")
      (node (ref "X1") (pin "17") (pinfunction "17_17") (pintype "bidirectional"))
    )
    (net (code "141") (name "SOLAR_CS4") (class "Default")
      (node (ref "X1") (pin "16") (pinfunction "16_16") (pintype "bidirectional"))
    )
    (net (code "142") (name "SOLAR_CS5") (class "Default")
      (node (ref "X1") (pin "18") (pinfunction "18_18") (pintype "bidirectional"))
    )
    (net (code "143") (name "SUN") (class "Default")
      (node (ref "X1") (pin "27") (pinfunction "27_27") (pintype "bidirectional"))
    )
    (net (code "144") (name "TEMP_ALERT") (class "Default")
      (node (ref "U8") (pin "3") (pinfunction "3_3") (pintype "bidirectional"))
    )
    (net (code "145") (name "TX_ON") (class "Default")
      (node (ref "U4") (pin "2") (pinfunction "P$2_2") (pintype "input"))
      (node (ref "U5") (pin "38") (pinfunction "38_38") (pintype "bidirectional"))
    )
    (net (code "146") (name "VAPC") (class "Default")
      (node (ref "C88") (pin "2") (pinfunction "2_2") (pintype "passive"))
      (node (ref "C89") (pin "2") (pinfunction "2_2") (pintype "passive"))
      (node (ref "U11") (pin "1") (pinfunction "OUT_1") (pintype "output"))
      (node (ref "U11") (pin "4") (pinfunction "-IN_4") (pintype "input"))
      (node (ref "U14") (pin "15") (pinfunction "P$15_15") (pintype "bidirectional"))
      (node (ref "U14") (pin "16") (pinfunction "P$16_16") (pintype "bidirectional"))
    )
    (net (code "147") (name "VBAT") (class "Default")
      (node (ref "X1") (pin "11") (pinfunction "11_11") (pintype "bidirectional"))
      (node (ref "X1") (pin "12") (pinfunction "12_12") (pintype "bidirectional"))
    )
    (net (code "148") (name "VBUS") (class "Default")
      (node (ref "R20") (pin "2") (pinfunction "2_2") (pintype "passive"))
      (node (ref "U1") (pin "1") (pinfunction "P$1_1") (pintype "input"))
      (node (ref "U1") (pin "2") (pinfunction "P$2_2") (pintype "input"))
      (node (ref "U9") (pin "1") (pinfunction "P$1_1") (pintype "power_in"))
      (node (ref "U9") (pin "12") (pinfunction "P$12_12") (pintype "power_in"))
      (node (ref "U9") (pin "13") (pinfunction "P$13_13") (pintype "power_in"))
      (node (ref "U9") (pin "16") (pinfunction "P$16_16") (pintype "power_in"))
      (node (ref "U9") (pin "4") (pinfunction "P$4_4") (pintype "power_in"))
      (node (ref "U9") (pin "5") (pinfunction "P$5_5") (pintype "power_in"))
      (node (ref "X1") (pin "10") (pinfunction "10_10") (pintype "bidirectional"))
      (node (ref "X1") (pin "7") (pinfunction "7_7") (pintype "bidirectional"))
      (node (ref "X1") (pin "8") (pinfunction "8_8") (pintype "bidirectional"))
      (node (ref "X1") (pin "9") (pinfunction "9_9") (pintype "bidirectional"))
    )
    (net (code "149") (name "VCCRF") (class "Default")
      (node (ref "C11") (pin "1") (pinfunction "1_1") (pintype "passive"))
      (node (ref "C12") (pin "P$1") (pinfunction "1_P$1") (pintype "passive"))
      (node (ref "C15") (pin "1") (pinfunction "1_1") (pintype "passive"))
      (node (ref "C17") (pin "1") (pinfunction "1_1") (pintype "passive"))
      (node (ref "C19") (pin "1") (pinfunction "1_1") (pintype "passive"))
      (node (ref "C22") (pin "1") (pinfunction "1_1") (pintype "passive"))
      (node (ref "C23") (pin "1") (pinfunction "1_1") (pintype "passive"))
      (node (ref "C24") (pin "1") (pinfunction "1_1") (pintype "passive"))
      (node (ref "C26") (pin "1") (pinfunction "1_1") (pintype "passive"))
      (node (ref "C28") (pin "1") (pinfunction "1_1") (pintype "passive"))
      (node (ref "C30") (pin "1") (pinfunction "1_1") (pintype "passive"))
      (node (ref "C33") (pin "1") (pinfunction "1_1") (pintype "passive"))
      (node (ref "C34") (pin "1") (pinfunction "1_1") (pintype "passive"))
      (node (ref "C35") (pin "1") (pinfunction "1_1") (pintype "passive"))
      (node (ref "C37") (pin "1") (pinfunction "1_1") (pintype "passive"))
      (node (ref "C38") (pin "1") (pinfunction "1_1") (pintype "passive"))
      (node (ref "C55") (pin "1") (pinfunction "1_1") (pintype "passive"))
      (node (ref "C66") (pin "1") (pinfunction "1_1") (pintype "passive"))
      (node (ref "C74") (pin "1") (pinfunction "1_1") (pintype "passive"))
      (node (ref "C75") (pin "1") (pinfunction "1_1") (pintype "passive"))
      (node (ref "L1") (pin "2") (pinfunction "2_2") (pintype "passive"))
      (node (ref "L13") (pin "2") (pinfunction "2_2") (pintype "passive"))
      (node (ref "TCXO2") (pin "4") (pinfunction "P$4_4") (pintype "bidirectional"))
      (node (ref "TCXO3") (pin "4") (pinfunction "P$4_4") (pintype "bidirectional"))
      (node (ref "U15") (pin "20") (pinfunction "P$20_20") (pintype "power_in"))
      (node (ref "U16") (pin "6") (pinfunction "6_6") (pintype "power_in"))
      (node (ref "U2") (pin "3") (pinfunction "P$3_3") (pintype "bidirectional"))
      (node (ref "U2") (pin "32") (pinfunction "P$32_32") (pintype "bidirectional"))
      (node (ref "U2") (pin "40") (pinfunction "P$40_40") (pintype "bidirectional"))
      (node (ref "U2") (pin "43") (pinfunction "P$43_43") (pintype "bidirectional"))
      (node (ref "U2") (pin "9") (pinfunction "P$9_9") (pintype "bidirectional"))
      (node (ref "U3") (pin "3") (pinfunction "P$3_3") (pintype "bidirectional"))
      (node (ref "U3") (pin "32") (pinfunction "P$32_32") (pintype "bidirectional"))
      (node (ref "U3") (pin "40") (pinfunction "P$40_40") (pintype "bidirectional"))
      (node (ref "U3") (pin "43") (pinfunction "P$43_43") (pintype "bidirectional"))
      (node (ref "U3") (pin "9") (pinfunction "P$9_9") (pintype "bidirectional"))
      (node (ref "U4") (pin "5") (pinfunction "P$5_5") (pintype "power_in"))
      (node (ref "U6") (pin "5") (pinfunction "P$5_5") (pintype "power_in"))
      (node (ref "U8") (pin "4") (pinfunction "4_4") (pintype "bidirectional"))
    )
    (net (code "150") (name "VCOMMS_PA") (class "Default")
      (node (ref "C59") (pin "P$1") (pinfunction "1_P$1") (pintype "passive"))
      (node (ref "C60") (pin "P$1") (pinfunction "1_P$1") (pintype "passive"))
      (node (ref "C62") (pin "1") (pinfunction "1_1") (pintype "passive"))
      (node (ref "C64") (pin "1") (pinfunction "1_1") (pintype "passive"))
      (node (ref "C68") (pin "1") (pinfunction "1_1") (pintype "passive"))
      (node (ref "C81") (pin "1") (pinfunction "1_1") (pintype "passive"))
      (node (ref "C82") (pin "1") (pinfunction "1_1") (pintype "passive"))
      (node (ref "C83") (pin "P$1") (pinfunction "1_P$1") (pintype "passive"))
      (node (ref "C87") (pin "2") (pinfunction "2_2") (pintype "passive"))
      (node (ref "C90") (pin "P$1") (pinfunction "1_P$1") (pintype "passive"))
      (node (ref "C91") (pin "1") (pinfunction "1_1") (pintype "passive"))
      (node (ref "C92") (pin "1") (pinfunction "1_1") (pintype "passive"))
      (node (ref "C94") (pin "1") (pinfunction "1_1") (pintype "passive"))
      (node (ref "C95") (pin "1") (pinfunction "1_1") (pintype "passive"))
      (node (ref "C96") (pin "1") (pinfunction "1_1") (pintype "passive"))
      (node (ref "L5") (pin "P$2") (pinfunction "2_P$2") (pintype "passive"))
      (node (ref "R22") (pin "1") (pinfunction "1_1") (pintype "passive"))
      (node (ref "R35") (pin "1") (pinfunction "1_1") (pintype "passive"))
      (node (ref "R36") (pin "2") (pinfunction "2_2") (pintype "passive"))
      (node (ref "R37") (pin "1") (pinfunction "1_1") (pintype "passive"))
      (node (ref "U10") (pin "6") (pinfunction "P$6_6") (pintype "power_in"))
      (node (ref "U10") (pin "7") (pinfunction "P$7_7") (pintype "power_in"))
      (node (ref "U11") (pin "5") (pinfunction "V+_5") (pintype "power_in"))
      (node (ref "U14") (pin "14") (pinfunction "P$14_14") (pintype "bidirectional"))
    )
    (net (code "151") (name "VSOLAR") (class "Default")
      (node (ref "X1") (pin "5") (pinfunction "5_5") (pintype "bidirectional"))
      (node (ref "X1") (pin "6") (pinfunction "6_6") (pintype "bidirectional"))
    )
    (net (code "152") (name "VSUPERCAP") (class "Default")
      (node (ref "X1") (pin "13") (pinfunction "13_13") (pintype "bidirectional"))
    )
    (net (code "153") (name "unconnected-(H1-MOUNT-PadB3,2)") (class "Default")
      (node (ref "H1") (pin "B3,2") (pinfunction "MOUNT_B3,2") (pintype "passive"))
    )
    (net (code "154") (name "unconnected-(H2-MOUNT-PadB3,2)") (class "Default")
      (node (ref "H2") (pin "B3,2") (pinfunction "MOUNT_B3,2") (pintype "passive"))
    )
    (net (code "155") (name "unconnected-(H3-MOUNT-PadB3,2)") (class "Default")
      (node (ref "H3") (pin "B3,2") (pinfunction "MOUNT_B3,2") (pintype "passive"))
    )
    (net (code "156") (name "unconnected-(H4-MOUNT-PadB3,2)") (class "Default")
      (node (ref "H4") (pin "B3,2") (pinfunction "MOUNT_B3,2") (pintype "passive"))
    )
    (net (code "157") (name "unconnected-(U2-P$13-Pad13)") (class "Default")
      (node (ref "U2") (pin "13") (pinfunction "P$13_13") (pintype "bidirectional"))
    )
    (net (code "158") (name "unconnected-(U2-P$14-Pad14)") (class "Default")
      (node (ref "U2") (pin "14") (pinfunction "P$14_14") (pintype "bidirectional"))
    )
    (net (code "159") (name "unconnected-(U2-P$15-Pad15)") (class "Default")
      (node (ref "U2") (pin "15") (pinfunction "P$15_15") (pintype "bidirectional"))
    )
    (net (code "160") (name "unconnected-(U2-P$16-Pad16)") (class "Default")
      (node (ref "U2") (pin "16") (pinfunction "P$16_16") (pintype "bidirectional"))
    )
    (net (code "161") (name "unconnected-(U2-P$17-Pad17)") (class "Default")
      (node (ref "U2") (pin "17") (pinfunction "P$17_17") (pintype "bidirectional"))
    )
    (net (code "162") (name "unconnected-(U2-P$18-Pad18)") (class "Default")
      (node (ref "U2") (pin "18") (pinfunction "P$18_18") (pintype "bidirectional"))
    )
    (net (code "163") (name "unconnected-(U2-P$20-Pad20)") (class "Default")
      (node (ref "U2") (pin "20") (pinfunction "P$20_20") (pintype "bidirectional"))
    )
    (net (code "164") (name "unconnected-(U2-P$21-Pad21)") (class "Default")
      (node (ref "U2") (pin "21") (pinfunction "P$21_21") (pintype "bidirectional"))
    )
    (net (code "165") (name "unconnected-(U2-P$23-Pad23)") (class "Default")
      (node (ref "U2") (pin "23") (pinfunction "P$23_23") (pintype "bidirectional"))
    )
    (net (code "166") (name "unconnected-(U2-P$30-Pad30)") (class "Default")
      (node (ref "U2") (pin "30") (pinfunction "P$30_30") (pintype "bidirectional"))
    )
    (net (code "167") (name "unconnected-(U2-P$33-Pad33)") (class "Default")
      (node (ref "U2") (pin "33") (pinfunction "P$33_33") (pintype "bidirectional"))
    )
    (net (code "168") (name "unconnected-(U2-P$38-Pad38)") (class "Default")
      (node (ref "U2") (pin "38") (pinfunction "P$38_38") (pintype "bidirectional"))
    )
    (net (code "169") (name "unconnected-(U2-P$44-Pad44)") (class "Default")
      (node (ref "U2") (pin "44") (pinfunction "P$44_44") (pintype "bidirectional"))
    )
    (net (code "170") (name "unconnected-(U2-P$46-Pad46)") (class "Default")
      (node (ref "U2") (pin "46") (pinfunction "P$46_46") (pintype "bidirectional"))
    )
    (net (code "171") (name "unconnected-(U3-P$4-Pad4)") (class "Default")
      (node (ref "U3") (pin "4") (pinfunction "P$4_4") (pintype "bidirectional"))
    )
    (net (code "172") (name "unconnected-(U3-P$13-Pad13)") (class "Default")
      (node (ref "U3") (pin "13") (pinfunction "P$13_13") (pintype "bidirectional"))
    )
    (net (code "173") (name "unconnected-(U3-P$14-Pad14)") (class "Default")
      (node (ref "U3") (pin "14") (pinfunction "P$14_14") (pintype "bidirectional"))
    )
    (net (code "174") (name "unconnected-(U3-P$15-Pad15)") (class "Default")
      (node (ref "U3") (pin "15") (pinfunction "P$15_15") (pintype "bidirectional"))
    )
    (net (code "175") (name "unconnected-(U3-P$16-Pad16)") (class "Default")
      (node (ref "U3") (pin "16") (pinfunction "P$16_16") (pintype "bidirectional"))
    )
    (net (code "176") (name "unconnected-(U3-P$17-Pad17)") (class "Default")
      (node (ref "U3") (pin "17") (pinfunction "P$17_17") (pintype "bidirectional"))
    )
    (net (code "177") (name "unconnected-(U3-P$18-Pad18)") (class "Default")
      (node (ref "U3") (pin "18") (pinfunction "P$18_18") (pintype "bidirectional"))
    )
    (net (code "178") (name "unconnected-(U3-P$20-Pad20)") (class "Default")
      (node (ref "U3") (pin "20") (pinfunction "P$20_20") (pintype "bidirectional"))
    )
    (net (code "179") (name "unconnected-(U3-P$21-Pad21)") (class "Default")
      (node (ref "U3") (pin "21") (pinfunction "P$21_21") (pintype "bidirectional"))
    )
    (net (code "180") (name "unconnected-(U3-P$23-Pad23)") (class "Default")
      (node (ref "U3") (pin "23") (pinfunction "P$23_23") (pintype "bidirectional"))
    )
    (net (code "181") (name "unconnected-(U3-P$30-Pad30)") (class "Default")
      (node (ref "U3") (pin "30") (pinfunction "P$30_30") (pintype "bidirectional"))
    )
    (net (code "182") (name "unconnected-(U3-P$38-Pad38)") (class "Default")
      (node (ref "U3") (pin "38") (pinfunction "P$38_38") (pintype "bidirectional"))
    )
    (net (code "183") (name "unconnected-(U3-P$44-Pad44)") (class "Default")
      (node (ref "U3") (pin "44") (pinfunction "P$44_44") (pintype "bidirectional"))
    )
    (net (code "184") (name "unconnected-(U3-P$46-Pad46)") (class "Default")
      (node (ref "U3") (pin "46") (pinfunction "P$46_46") (pintype "bidirectional"))
    )
    (net (code "185") (name "unconnected-(U4-P$1-Pad1)") (class "Default")
      (node (ref "U4") (pin "1") (pinfunction "P$1_1") (pintype "no_connect"))
    )
    (net (code "186") (name "unconnected-(U5-Pad3)") (class "Default")
      (node (ref "U5") (pin "3") (pinfunction "3_3") (pintype "bidirectional"))
    )
    (net (code "187") (name "unconnected-(U5-Pad4)") (class "Default")
      (node (ref "U5") (pin "4") (pinfunction "4_4") (pintype "bidirectional"))
    )
    (net (code "188") (name "unconnected-(U5-Pad6)") (class "Default")
      (node (ref "U5") (pin "6") (pinfunction "6_6") (pintype "bidirectional"))
    )
    (net (code "189") (name "unconnected-(U5-Pad10)") (class "Default")
      (node (ref "U5") (pin "10") (pinfunction "10_10") (pintype "input"))
    )
    (net (code "190") (name "unconnected-(U5-Pad11)") (class "Default")
      (node (ref "U5") (pin "11") (pinfunction "11_11") (pintype "bidirectional"))
    )
    (net (code "191") (name "unconnected-(U5-Pad28)") (class "Default")
      (node (ref "U5") (pin "28") (pinfunction "28_28") (pintype "bidirectional"))
    )
    (net (code "192") (name "unconnected-(U5-Pad30)") (class "Default")
      (node (ref "U5") (pin "30") (pinfunction "30_30") (pintype "bidirectional"))
    )
    (net (code "193") (name "unconnected-(U5-Pad32)") (class "Default")
      (node (ref "U5") (pin "32") (pinfunction "32_32") (pintype "bidirectional"))
    )
    (net (code "194") (name "unconnected-(U5-Pad33)") (class "Default")
      (node (ref "U5") (pin "33") (pinfunction "33_33") (pintype "bidirectional"))
    )
    (net (code "195") (name "unconnected-(U5-Pad41)") (class "Default")
      (node (ref "U5") (pin "41") (pinfunction "41_41") (pintype "bidirectional"))
    )
    (net (code "196") (name "unconnected-(U5-Pad42)") (class "Default")
      (node (ref "U5") (pin "42") (pinfunction "42_42") (pintype "bidirectional"))
    )
    (net (code "197") (name "unconnected-(U5-Pad43)") (class "Default")
      (node (ref "U5") (pin "43") (pinfunction "43_43") (pintype "bidirectional"))
    )
    (net (code "198") (name "unconnected-(U5-Pad44)") (class "Default")
      (node (ref "U5") (pin "44") (pinfunction "44_44") (pintype "bidirectional"))
    )
    (net (code "199") (name "unconnected-(U5-Pad45)") (class "Default")
      (node (ref "U5") (pin "45") (pinfunction "45_45") (pintype "bidirectional"))
    )
    (net (code "200") (name "unconnected-(U5-Pad46)") (class "Default")
      (node (ref "U5") (pin "46") (pinfunction "46_46") (pintype "bidirectional"))
    )
    (net (code "201") (name "unconnected-(U5-Pad47)") (class "Default")
      (node (ref "U5") (pin "47") (pinfunction "47_47") (pintype "bidirectional"))
    )
    (net (code "202") (name "unconnected-(U5-Pad48)") (class "Default")
      (node (ref "U5") (pin "48") (pinfunction "48_48") (pintype "bidirectional"))
    )
    (net (code "203") (name "unconnected-(U5-Pad51)") (class "Default")
      (node (ref "U5") (pin "51") (pinfunction "51_51") (pintype "bidirectional"))
    )
    (net (code "204") (name "unconnected-(U5-Pad52)") (class "Default")
      (node (ref "U5") (pin "52") (pinfunction "52_52") (pintype "output"))
    )
    (net (code "205") (name "unconnected-(U5-Pad59)") (class "Default")
      (node (ref "U5") (pin "59") (pinfunction "59_59") (pintype "bidirectional"))
    )
    (net (code "206") (name "unconnected-(U5-Pad60)") (class "Default")
      (node (ref "U5") (pin "60") (pinfunction "60_60") (pintype "bidirectional"))
    )
    (net (code "207") (name "unconnected-(U5-Pad61)") (class "Default")
      (node (ref "U5") (pin "61") (pinfunction "61_61") (pintype "bidirectional"))
    )
    (net (code "208") (name "unconnected-(U6-P$1-Pad1)") (class "Default")
      (node (ref "U6") (pin "1") (pinfunction "P$1_1") (pintype "no_connect"))
    )
    (net (code "209") (name "unconnected-(U8-Pad5)") (class "Default")
      (node (ref "U8") (pin "5") (pinfunction "5_5") (pintype "bidirectional"))
    )
    (net (code "210") (name "unconnected-(U12-Pad4)") (class "Default")
      (node (ref "U12") (pin "4") (pinfunction "4_4") (pintype "passive"))
    )
    (net (code "211") (name "unconnected-(U14-P$7-Pad7)") (class "Default")
      (node (ref "U14") (pin "7") (pinfunction "P$7_7") (pintype "bidirectional"))
    )
    (net (code "212") (name "unconnected-(U14-P$8-Pad8)") (class "Default")
      (node (ref "U14") (pin "8") (pinfunction "P$8_8") (pintype "bidirectional"))
    )
    (net (code "213") (name "unconnected-(U14-P$13-Pad13)") (class "Default")
      (node (ref "U14") (pin "13") (pinfunction "P$13_13") (pintype "bidirectional"))
    )
    (net (code "214") (name "unconnected-(X1-Pad3)") (class "Default")
      (node (ref "X1") (pin "3") (pinfunction "3_3") (pintype "bidirectional"))
    )
    (net (code "215") (name "unconnected-(X1-Pad4)") (class "Default")
      (node (ref "X1") (pin "4") (pinfunction "4_4") (pintype "bidirectional"))
    )
    (net (code "216") (name "unconnected-(X2-Pad2)") (class "Default")
      (node (ref "X2") (pin "2") (pinfunction "2_2") (pintype "bidirectional"))
    )
    (net (code "217") (name "unconnected-(X2-Pad6)") (class "Default")
      (node (ref "X2") (pin "6") (pinfunction "6_6") (pintype "bidirectional"))
    )
    (net (code "218") (name "unconnected-(X2-Pad8)") (class "Default")
      (node (ref "X2") (pin "8") (pinfunction "8_8") (pintype "bidirectional"))
    )
    (net (code "219") (name "{slash}RST") (class "Default")
      (node (ref "R2") (pin "1") (pinfunction "1_1") (pintype "passive"))
      (node (ref "R8") (pin "2") (pinfunction "2_2") (pintype "passive"))
      (node (ref "U5") (pin "58") (pinfunction "58_58") (pintype "input"))
      (node (ref "U7") (pin "4") (pinfunction "P$4_4") (pintype "output"))
    )
  )
)
